# MSP-EXP430F5529LP.net
KiCad netlist of a schematic drawn in EAGLE
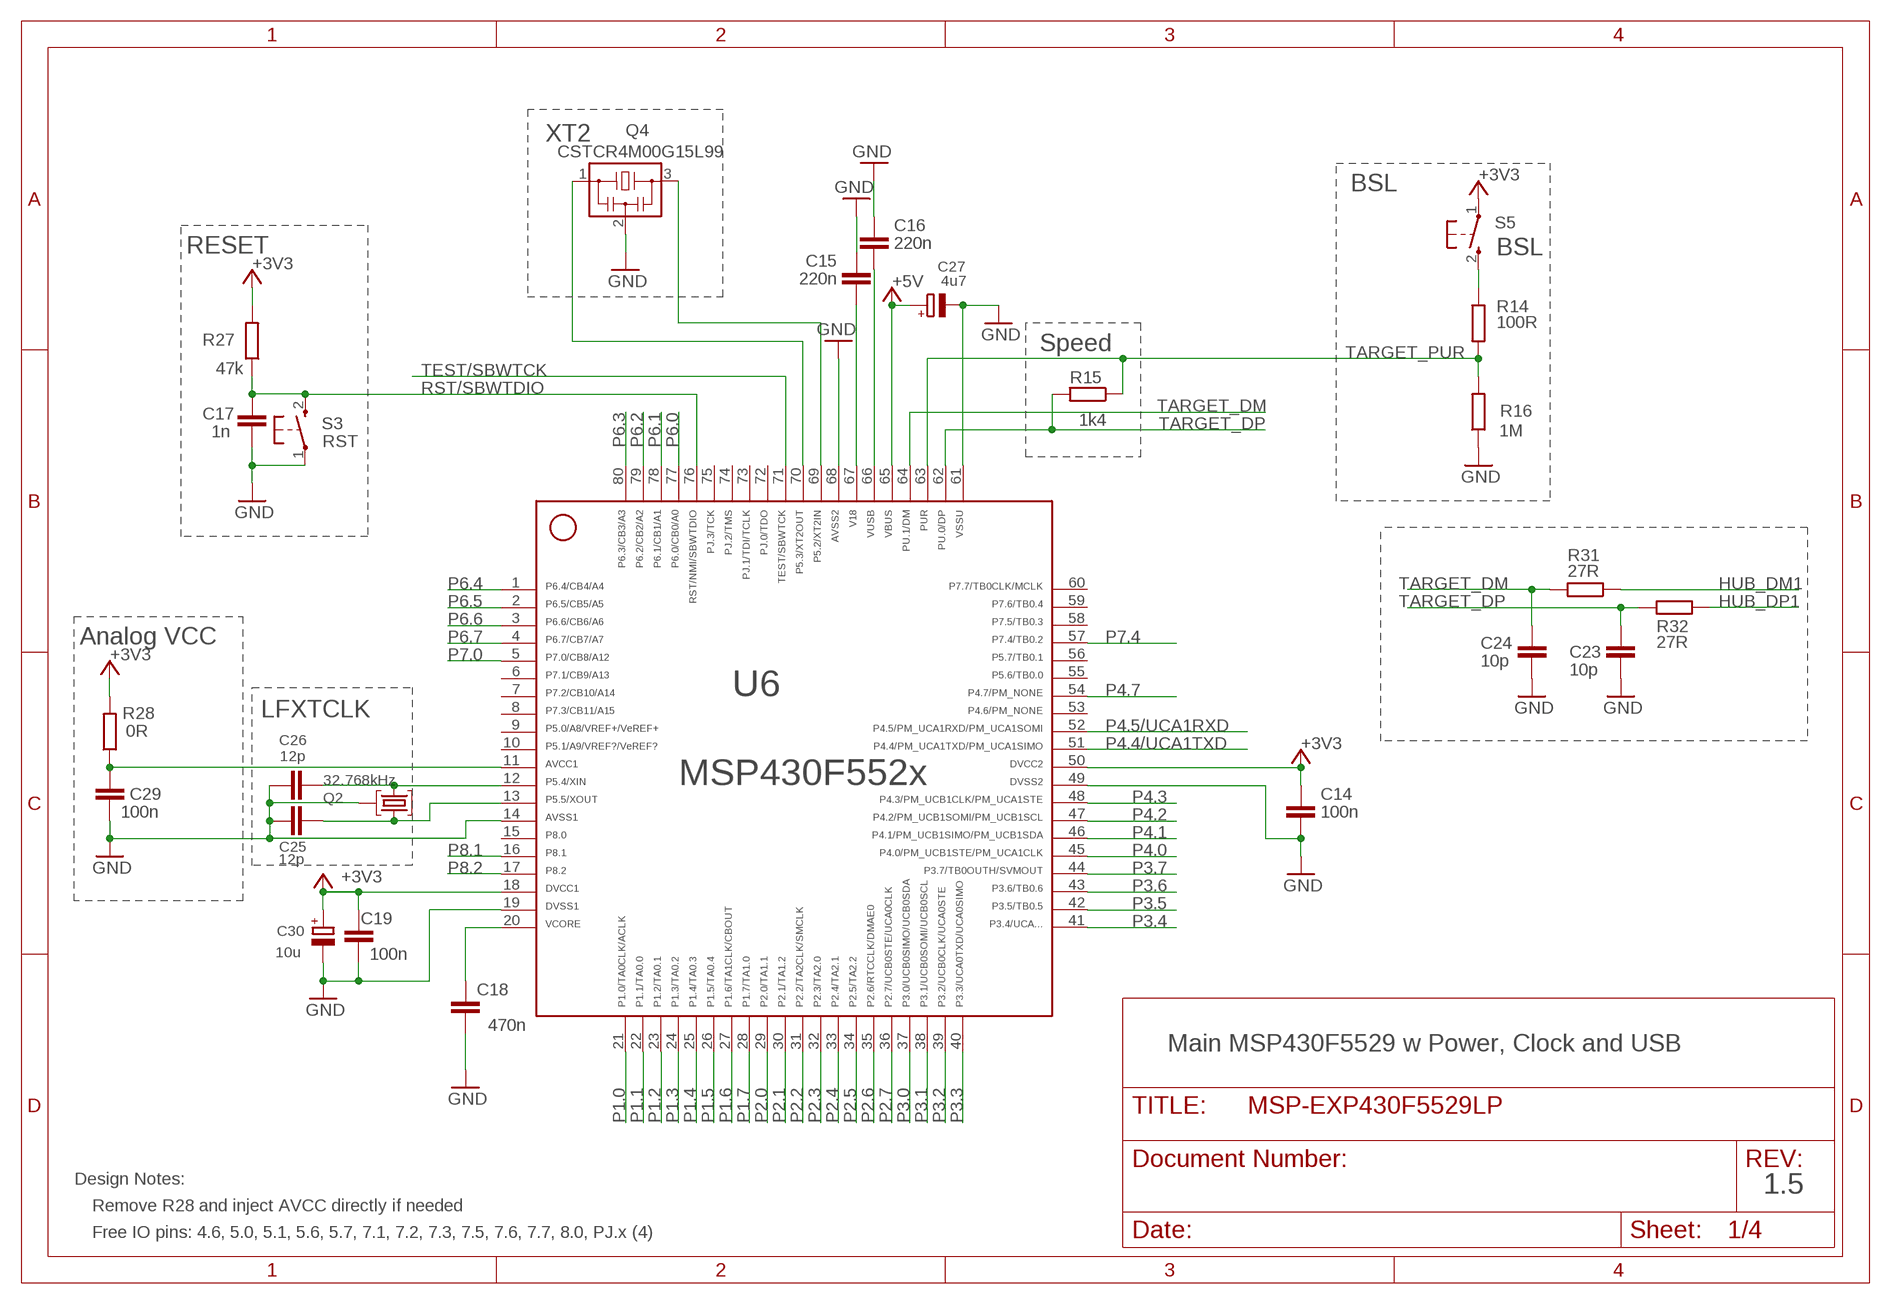
[diagram p0: schematic, sheet 1]
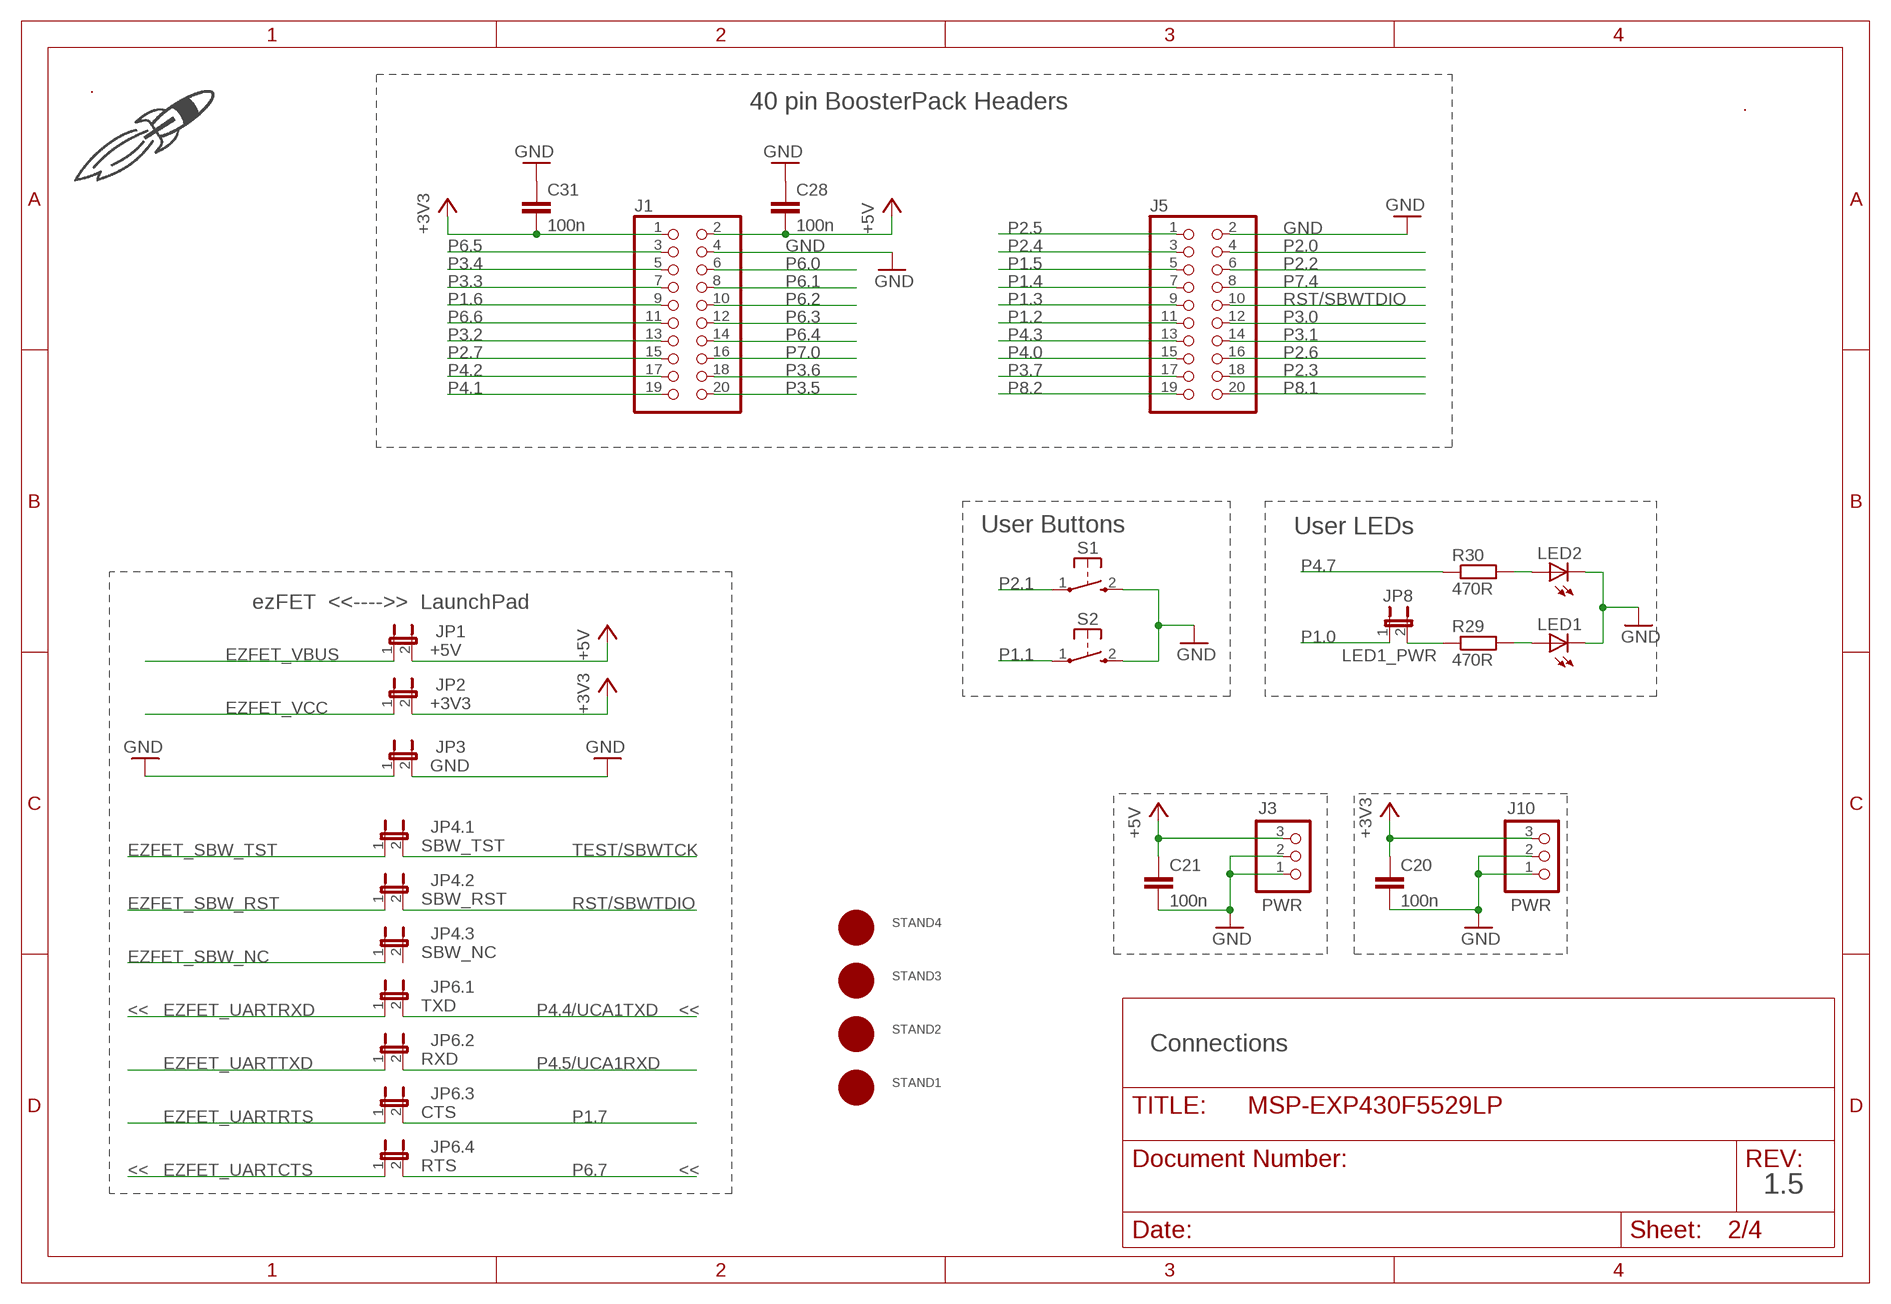
[diagram p1: schematic, sheet 2]
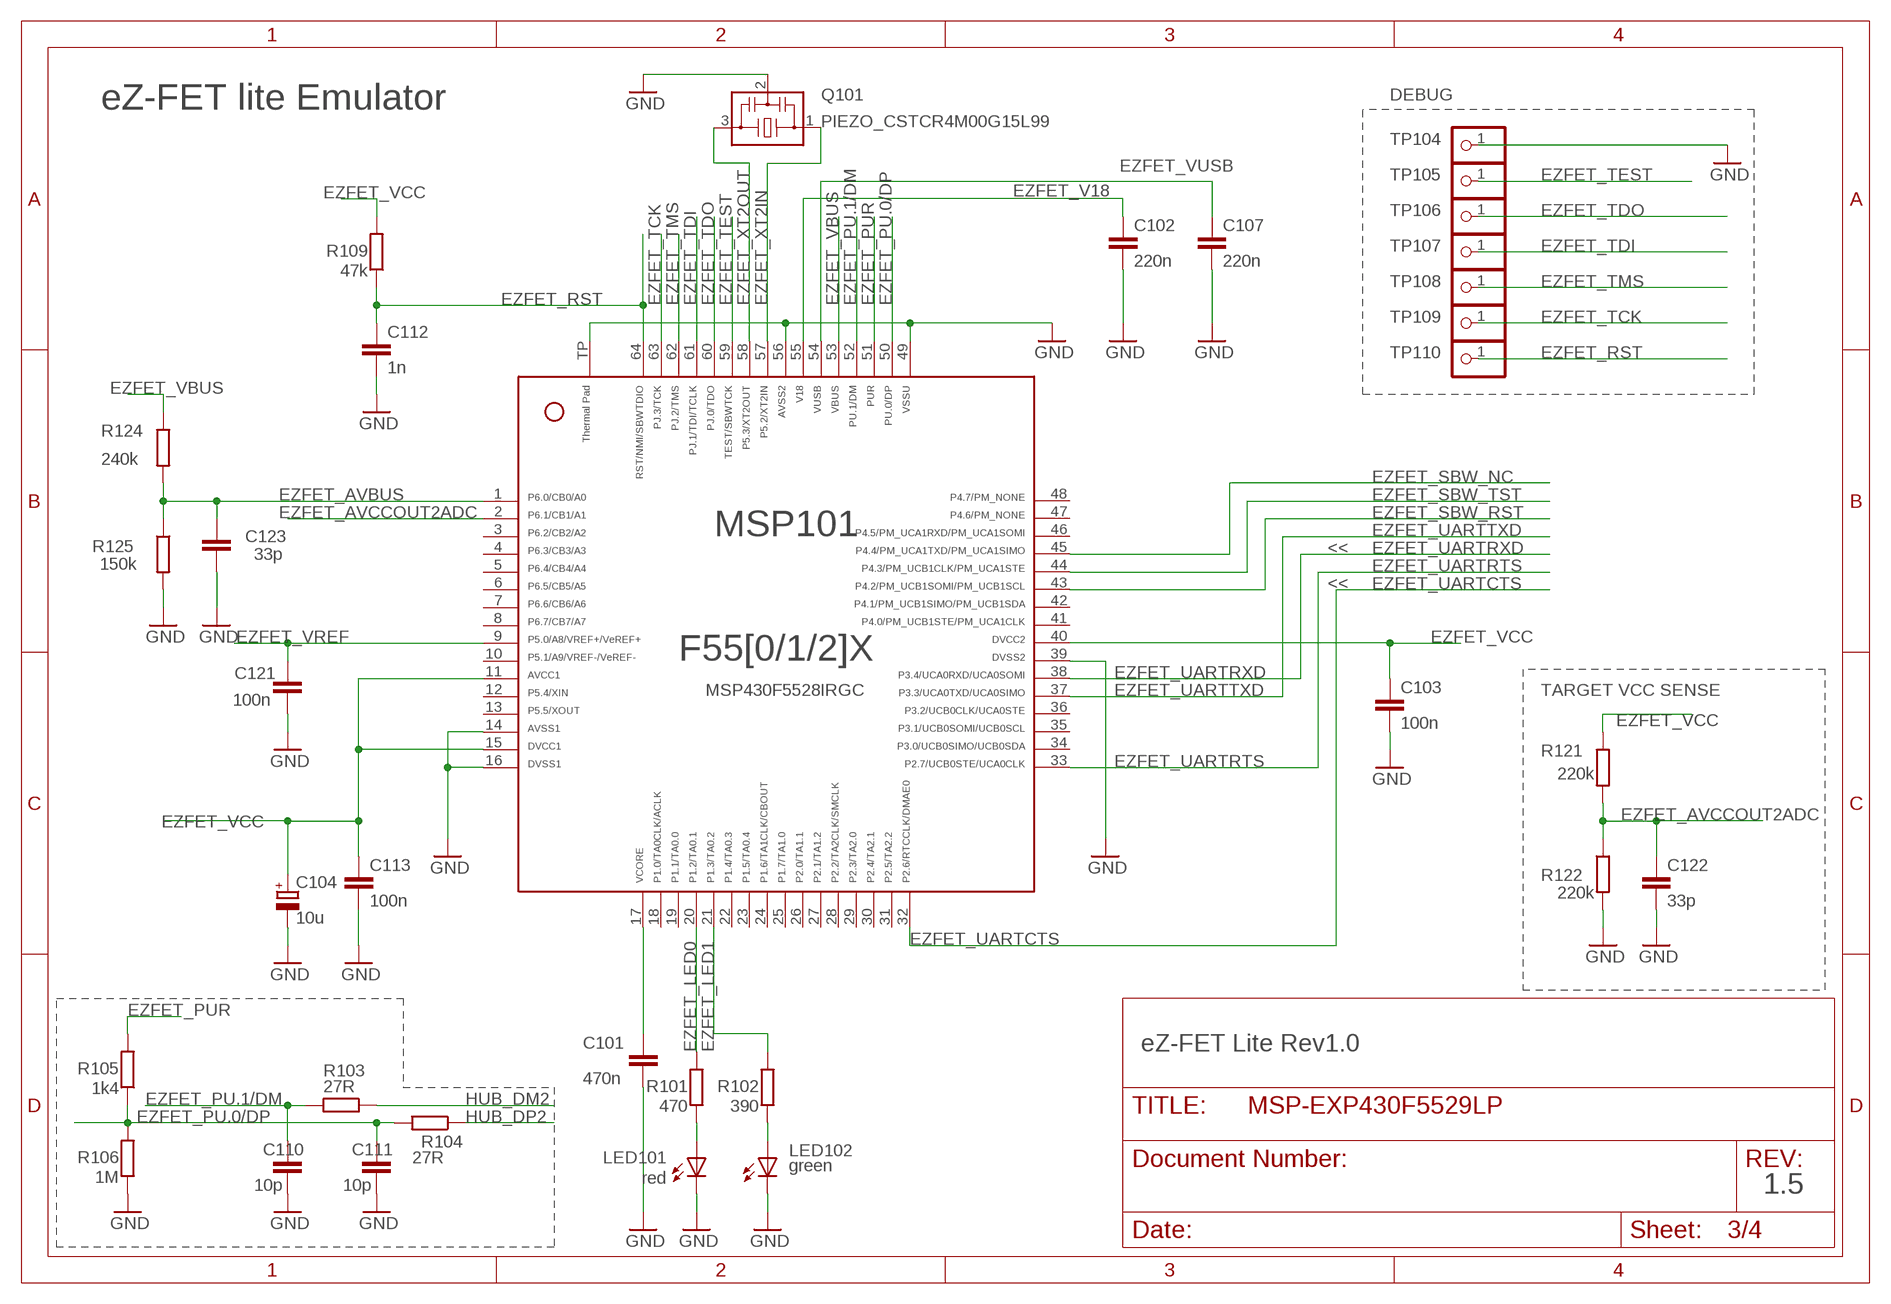
[diagram p2: schematic, sheet 3]
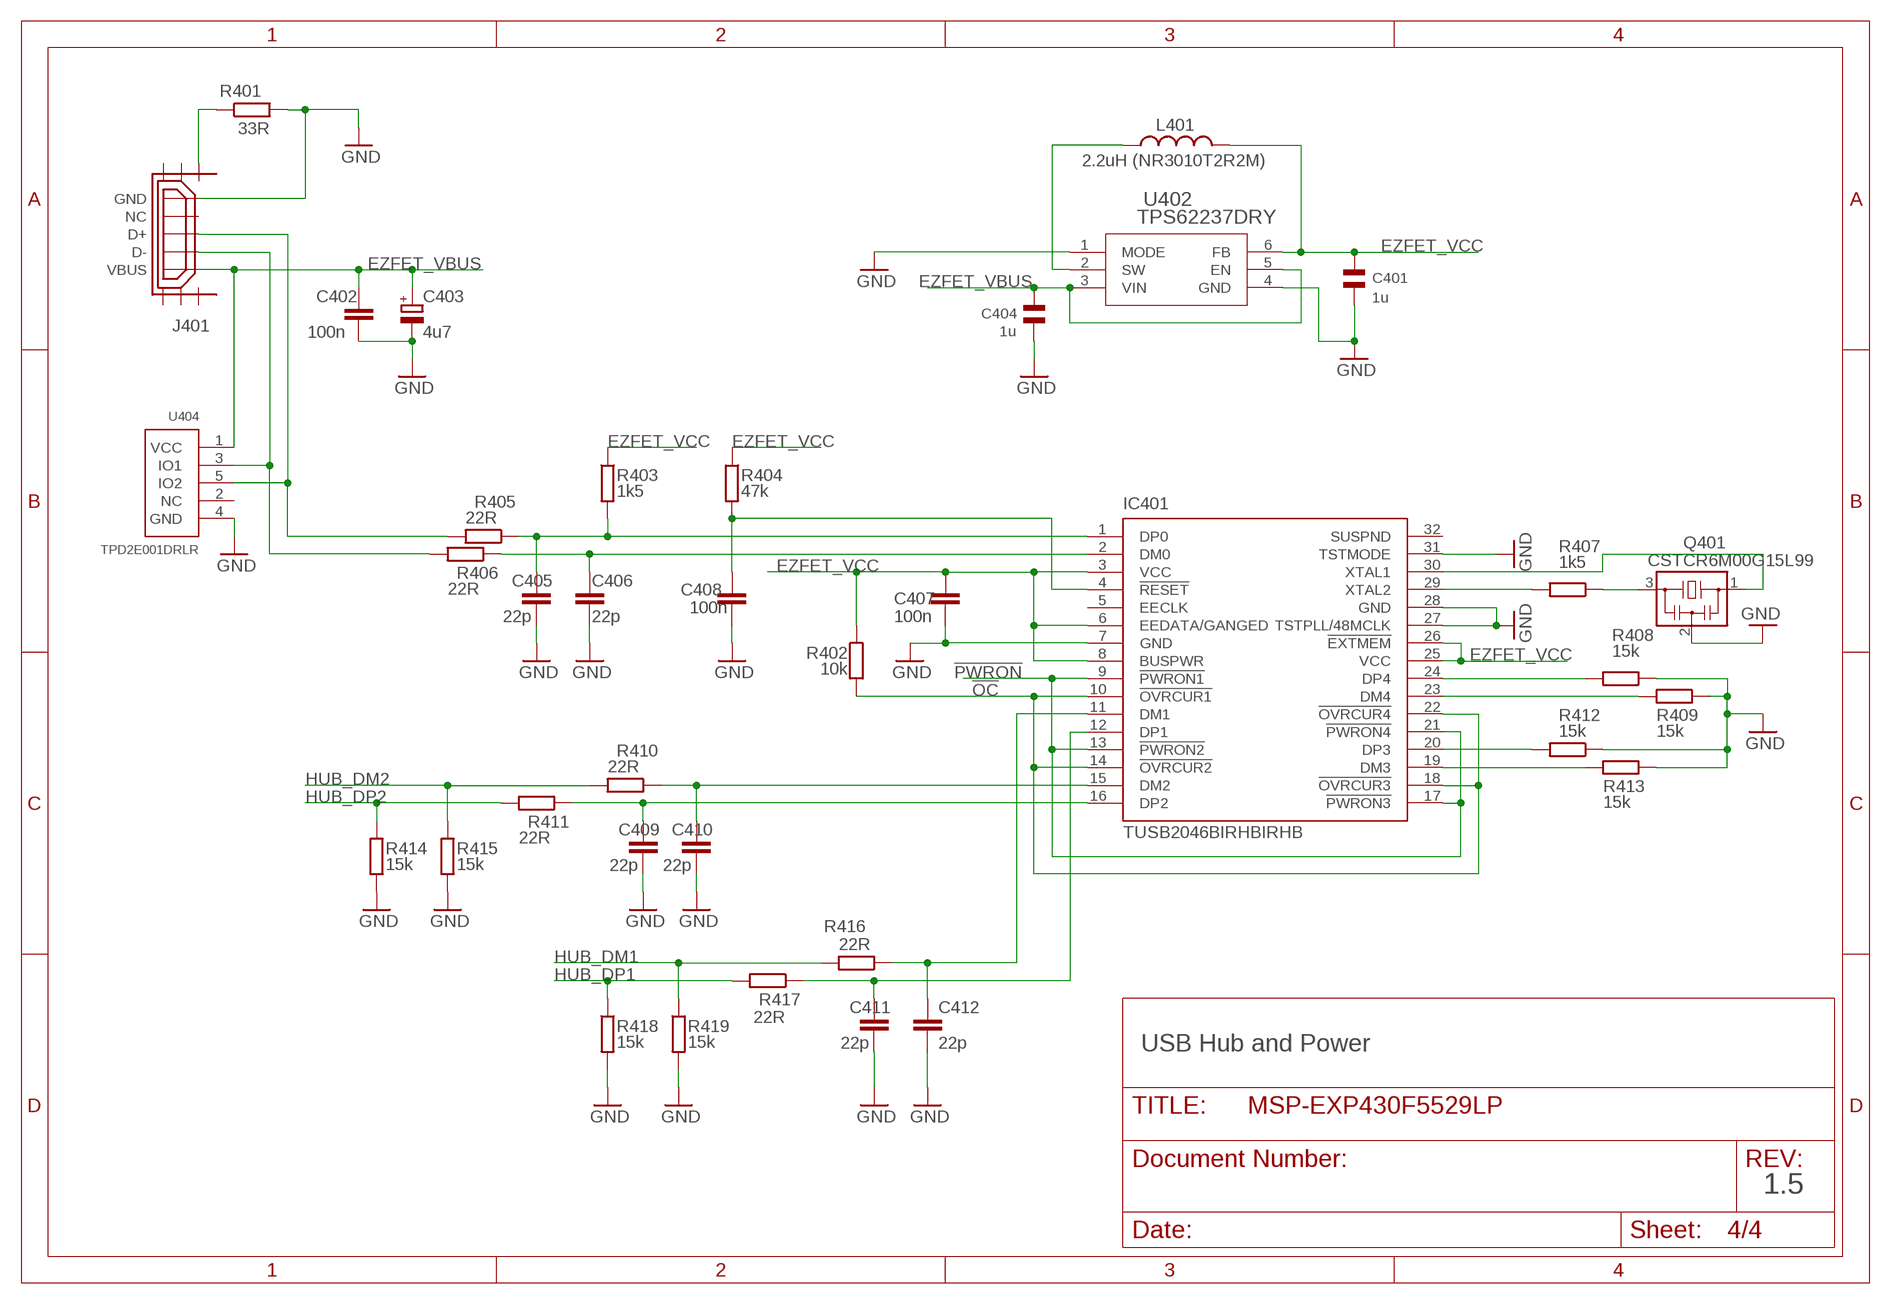
[diagram p3: schematic, sheet 4]

(export (version "E")
  (design (tool "Eeschema 10.0.6"))
  (components
    (comp (ref "C20")
      (value "100n")
      (footprint "eagle-import:C0402")
      (libsource (lib "eagle-import") (part "C-EUC0402"))
    )
    (comp (ref "C21")
      (value "100n")
      (footprint "eagle-import:C0402")
      (libsource (lib "eagle-import") (part "C-EUC0402"))
    )
    (comp (ref "C28")
      (value "100n")
      (footprint "eagle-import:C0402")
      (libsource (lib "eagle-import") (part "C-EUC0402"))
    )
    (comp (ref "C31")
      (value "100n")
      (footprint "eagle-import:C0402")
      (libsource (lib "eagle-import") (part "C-EUC0402"))
    )
    (comp (ref "DRAW1")
      (value "LOGO-ROCKET-20X13MM-SCH-S")
      (footprint "eagle-import:LOGO-ROCKET-10X7MM-BRD")
      (libsource (lib "eagle-import") (part "LOGO-ROCKET-20X13MM-SCH-S"))
    )
    (comp (ref "J1")
      (value "PINHD-2X10")
      (footprint "eagle-import:2X10")
      (libsource (lib "eagle-import") (part "PINHD-2X10"))
    )
    (comp (ref "J3")
      (value "PWR")
      (footprint "eagle-import:1X03")
      (libsource (lib "eagle-import") (part "PINHD-1X3"))
    )
    (comp (ref "J5")
      (value "PINHD-2X10")
      (footprint "eagle-import:2X10")
      (libsource (lib "eagle-import") (part "PINHD-2X10"))
    )
    (comp (ref "J10")
      (value "PWR")
      (footprint "eagle-import:1X03")
      (libsource (lib "eagle-import") (part "PINHD-1X3"))
    )
    (comp (ref "JP1")
      (value "+5V")
      (footprint "eagle-import:JP1M")
      (libsource (lib "eagle-import") (part "JP1M"))
    )
    (comp (ref "JP2")
      (value "+3V3")
      (footprint "eagle-import:JP1M")
      (libsource (lib "eagle-import") (part "JP1M"))
    )
    (comp (ref "JP3")
      (value "GND")
      (footprint "eagle-import:JP1M")
      (libsource (lib "eagle-import") (part "JP1M"))
    )
    (comp (ref "JP4.1")
      (value "SBW_TST")
      (footprint "eagle-import:JP1M")
      (libsource (lib "eagle-import") (part "JP1M"))
    )
    (comp (ref "JP4.2")
      (value "SBW_RST")
      (footprint "eagle-import:JP1M")
      (libsource (lib "eagle-import") (part "JP1M"))
    )
    (comp (ref "JP4.3")
      (value "SBW_NC")
      (footprint "eagle-import:JP1M")
      (libsource (lib "eagle-import") (part "JP1M"))
    )
    (comp (ref "JP6.1")
      (value "TXD")
      (footprint "eagle-import:JP1M")
      (libsource (lib "eagle-import") (part "JP1M"))
    )
    (comp (ref "JP6.2")
      (value "RXD")
      (footprint "eagle-import:JP1M")
      (libsource (lib "eagle-import") (part "JP1M"))
    )
    (comp (ref "JP6.3")
      (value "CTS")
      (footprint "eagle-import:JP1M")
      (libsource (lib "eagle-import") (part "JP1M"))
    )
    (comp (ref "JP6.4")
      (value "RTS")
      (footprint "eagle-import:JP1M")
      (libsource (lib "eagle-import") (part "JP1M"))
    )
    (comp (ref "JP8")
      (value "LED1_PWR")
      (footprint "eagle-import:JP1")
      (libsource (lib "eagle-import") (part "JP1E"))
    )
    (comp (ref "LED1")
      (value "LEDCHIP-LED0603")
      (footprint "eagle-import:CHIP-LED0603")
      (libsource (lib "eagle-import") (part "LEDCHIP-LED0603"))
    )
    (comp (ref "LED2")
      (value "LEDCHIP-LED0603")
      (footprint "eagle-import:CHIP-LED0603")
      (libsource (lib "eagle-import") (part "LEDCHIP-LED0603"))
    )
    (comp (ref "R29")
      (value "470R")
      (footprint "eagle-import:R0402")
      (libsource (lib "eagle-import") (part "R-EU_R0402"))
    )
    (comp (ref "R30")
      (value "470R")
      (footprint "eagle-import:R0402")
      (libsource (lib "eagle-import") (part "R-EU_R0402"))
    )
    (comp (ref "S1")
      (value "PB")
      (footprint "eagle-import:PBTH")
      (libsource (lib "eagle-import") (part "PB"))
    )
    (comp (ref "S2")
      (value "PB")
      (footprint "eagle-import:PBTH")
      (libsource (lib "eagle-import") (part "PB"))
    )
    (comp (ref "STAND1")
      (value "MOUNT")
      (footprint "eagle-import:MOUNTHOLE_110MIL")
      (libsource (lib "eagle-import") (part "MOUNT"))
    )
    (comp (ref "STAND2")
      (value "MOUNT")
      (footprint "eagle-import:MOUNTHOLE_110MIL")
      (libsource (lib "eagle-import") (part "MOUNT"))
    )
    (comp (ref "STAND3")
      (value "MOUNT")
      (footprint "eagle-import:MOUNTHOLE_110MIL")
      (libsource (lib "eagle-import") (part "MOUNT"))
    )
    (comp (ref "STAND4")
      (value "MOUNT")
      (footprint "eagle-import:MOUNTHOLE_110MIL")
      (libsource (lib "eagle-import") (part "MOUNT"))
    )
    (comp (ref "U$3")
      (value "5529_REAR_SILK_REV1_5_FINAL")
      (footprint "eagle-import:5529_REAR_SILK_REV1_5_FINAL")
      (libsource (lib "eagle-import") (part "5529_REAR_SILK_REV1_5_FINAL"))
    )
    (comp (ref "U$4")
      (value "MS_TM")
      (footprint "eagle-import:MS_TM")
      (libsource (lib "eagle-import") (part "MS_TM"))
    )
    (comp (ref "C14")
      (value "100n")
      (footprint "eagle-import:C0402")
      (libsource (lib "eagle-import") (part "C-EUC0402"))
    )
    (comp (ref "C15")
      (value "220n")
      (footprint "eagle-import:C0402")
      (libsource (lib "eagle-import") (part "C-EUC0402"))
    )
    (comp (ref "C16")
      (value "220n")
      (footprint "eagle-import:C0402")
      (libsource (lib "eagle-import") (part "C-EUC0402"))
    )
    (comp (ref "C17")
      (value "1n")
      (footprint "eagle-import:C0402")
      (libsource (lib "eagle-import") (part "C-EUC0402"))
    )
    (comp (ref "C18")
      (value "470n")
      (footprint "eagle-import:C0402")
      (libsource (lib "eagle-import") (part "C-EUC0402"))
    )
    (comp (ref "C19")
      (value "100n")
      (footprint "eagle-import:C0402")
      (libsource (lib "eagle-import") (part "C-EUC0402"))
    )
    (comp (ref "C23")
      (value "10p")
      (footprint "eagle-import:C0402")
      (libsource (lib "eagle-import") (part "C-EUC0402"))
    )
    (comp (ref "C24")
      (value "10p")
      (footprint "eagle-import:C0402")
      (libsource (lib "eagle-import") (part "C-EUC0402"))
    )
    (comp (ref "C25")
      (value "12p")
      (footprint "eagle-import:C0402")
      (libsource (lib "eagle-import") (part "C-EUC0402"))
    )
    (comp (ref "C26")
      (value "12p")
      (footprint "eagle-import:C0402")
      (libsource (lib "eagle-import") (part "C-EUC0402"))
    )
    (comp (ref "C27")
      (value "4u7")
      (footprint "eagle-import:A_3216-18R")
      (libsource (lib "eagle-import") (part "CPOL-EUA/3216-18R"))
    )
    (comp (ref "C29")
      (value "100n")
      (footprint "eagle-import:C0402")
      (libsource (lib "eagle-import") (part "C-EUC0402"))
    )
    (comp (ref "C30")
      (value "10u")
      (footprint "eagle-import:A_3216-18R")
      (libsource (lib "eagle-import") (part "CPOL-EUA/3216-18R"))
    )
    (comp (ref "Q2")
      (value "32.768kHz")
      (footprint "eagle-import:MS3V-T1R")
      (libsource (lib "eagle-import") (part "MS3V-T1R"))
    )
    (comp (ref "Q4")
      (value "CSTCR4M00G15L99")
      (footprint "eagle-import:MURATA-FILTER_CSTCR")
      (fields (field (name "MPN") "CSTCR6M00G53-R0"))
      (libsource (lib "eagle-import") (part "MURATA-FILTER_CSTCR6M00G53Z"))
    )
    (comp (ref "R14")
      (value "100R")
      (footprint "eagle-import:R0402")
      (libsource (lib "eagle-import") (part "R-EU_R0402"))
    )
    (comp (ref "R15")
      (value "1k4")
      (footprint "eagle-import:R0402")
      (libsource (lib "eagle-import") (part "R-EU_R0402"))
    )
    (comp (ref "R16")
      (value "1M")
      (footprint "eagle-import:R0402")
      (libsource (lib "eagle-import") (part "R-EU_R0402"))
    )
    (comp (ref "R27")
      (value "47k")
      (footprint "eagle-import:R0402")
      (libsource (lib "eagle-import") (part "R-EU_R0402"))
    )
    (comp (ref "R28")
      (value "0R")
      (footprint "eagle-import:R0402")
      (libsource (lib "eagle-import") (part "R-EU_R0402"))
    )
    (comp (ref "R31")
      (value "27R")
      (footprint "eagle-import:R0402")
      (libsource (lib "eagle-import") (part "R-EU_R0402"))
    )
    (comp (ref "R32")
      (value "27R")
      (footprint "eagle-import:R0402")
      (libsource (lib "eagle-import") (part "R-EU_R0402"))
    )
    (comp (ref "S3")
      (value "RST")
      (footprint "eagle-import:PBTH")
      (libsource (lib "eagle-import") (part "PB"))
    )
    (comp (ref "S5")
      (value "BSL")
      (footprint "eagle-import:PBTH")
      (libsource (lib "eagle-import") (part "PB"))
    )
    (comp (ref "U6")
      (value "MSP430F5529IPNR")
      (footprint "eagle-import:PN80")
      (libsource (lib "eagle-import") (part "F552X---PN80"))
    )
    (comp (ref "C101")
      (value "470n")
      (footprint "eagle-import:C0402")
      (libsource (lib "eagle-import") (part "C-EUC0402"))
    )
    (comp (ref "C102")
      (value "220n")
      (footprint "eagle-import:C0402")
      (libsource (lib "eagle-import") (part "C-EUC0402"))
    )
    (comp (ref "C103")
      (value "100n")
      (footprint "eagle-import:C0402")
      (libsource (lib "eagle-import") (part "C-EUC0402"))
    )
    (comp (ref "C104")
      (value "10u")
      (footprint "eagle-import:A_3216-18R")
      (libsource (lib "eagle-import") (part "CPOL-EUA/3216-18R"))
    )
    (comp (ref "C107")
      (value "220n")
      (footprint "eagle-import:C0402")
      (libsource (lib "eagle-import") (part "C-EUC0402"))
    )
    (comp (ref "C110")
      (value "10p")
      (footprint "eagle-import:C0402")
      (libsource (lib "eagle-import") (part "C-EUC0402"))
    )
    (comp (ref "C111")
      (value "10p")
      (footprint "eagle-import:C0402")
      (libsource (lib "eagle-import") (part "C-EUC0402"))
    )
    (comp (ref "C112")
      (value "1n")
      (footprint "eagle-import:C0402")
      (libsource (lib "eagle-import") (part "C-EUC0402"))
    )
    (comp (ref "C113")
      (value "100n")
      (footprint "eagle-import:C0402")
      (libsource (lib "eagle-import") (part "C-EUC0402"))
    )
    (comp (ref "C121")
      (value "100n")
      (footprint "eagle-import:C0402")
      (libsource (lib "eagle-import") (part "C-EUC0402"))
    )
    (comp (ref "C122")
      (value "33p")
      (footprint "eagle-import:C0402")
      (libsource (lib "eagle-import") (part "C-EUC0402"))
    )
    (comp (ref "C123")
      (value "33p")
      (footprint "eagle-import:C0402")
      (libsource (lib "eagle-import") (part "C-EUC0402"))
    )
    (comp (ref "LED101")
      (value "red")
      (footprint "eagle-import:CHIP-LED0603")
      (libsource (lib "eagle-import") (part "LEDCHIP-LED0603"))
    )
    (comp (ref "LED102")
      (value "green")
      (footprint "eagle-import:CHIP-LED0603")
      (libsource (lib "eagle-import") (part "LEDCHIP-LED0603"))
    )
    (comp (ref "MSP101")
      (value "MSP430F5528IRGC")
      (footprint "eagle-import:RGC64")
      (libsource (lib "eagle-import") (part "F55[0/1/2]X---RGC64"))
    )
    (comp (ref "Q101")
      (value "PIEZO_CSTCR4M00G15L99")
      (footprint "eagle-import:MURATA-FILTER_CSTCR")
      (fields (field (name "MPN") "CSTCR6M00G53-R0"))
      (libsource (lib "eagle-import") (part "MURATA-FILTER_CSTCR6M00G53Z"))
    )
    (comp (ref "R101")
      (value "470")
      (footprint "eagle-import:R0402")
      (libsource (lib "eagle-import") (part "R-EU_R0402"))
    )
    (comp (ref "R102")
      (value "390")
      (footprint "eagle-import:R0402")
      (libsource (lib "eagle-import") (part "R-EU_R0402"))
    )
    (comp (ref "R103")
      (value "27R")
      (footprint "eagle-import:R0402")
      (libsource (lib "eagle-import") (part "R-EU_R0402"))
    )
    (comp (ref "R104")
      (value "27R")
      (footprint "eagle-import:R0402")
      (libsource (lib "eagle-import") (part "R-EU_R0402"))
    )
    (comp (ref "R105")
      (value "1k4")
      (footprint "eagle-import:R0402")
      (libsource (lib "eagle-import") (part "R-EU_R0402"))
    )
    (comp (ref "R106")
      (value "1M")
      (footprint "eagle-import:R0402")
      (libsource (lib "eagle-import") (part "R-EU_R0402"))
    )
    (comp (ref "R109")
      (value "47k")
      (footprint "eagle-import:R0402")
      (libsource (lib "eagle-import") (part "R-EU_R0402"))
    )
    (comp (ref "R121")
      (value "220k")
      (footprint "eagle-import:R0402")
      (libsource (lib "eagle-import") (part "R-EU_R0402"))
    )
    (comp (ref "R122")
      (value "220k")
      (footprint "eagle-import:R0402")
      (libsource (lib "eagle-import") (part "R-EU_R0402"))
    )
    (comp (ref "R124")
      (value "240k")
      (footprint "eagle-import:R0402")
      (libsource (lib "eagle-import") (part "R-EU_R0402"))
    )
    (comp (ref "R125")
      (value "150k")
      (footprint "eagle-import:R0402")
      (libsource (lib "eagle-import") (part "R-EU_R0402"))
    )
    (comp (ref "TP104")
      (value "TEST_PIN2")
      (footprint "eagle-import:1X01")
      (libsource (lib "eagle-import") (part "PINHD-1X1"))
    )
    (comp (ref "TP105")
      (value "TEST_PIN2")
      (footprint "eagle-import:1X01")
      (libsource (lib "eagle-import") (part "PINHD-1X1"))
    )
    (comp (ref "TP106")
      (value "TEST_PIN2")
      (footprint "eagle-import:1X01")
      (libsource (lib "eagle-import") (part "PINHD-1X1"))
    )
    (comp (ref "TP107")
      (value "TEST_PIN2")
      (footprint "eagle-import:1X01")
      (libsource (lib "eagle-import") (part "PINHD-1X1"))
    )
    (comp (ref "TP108")
      (value "TEST_PIN2")
      (footprint "eagle-import:1X01")
      (libsource (lib "eagle-import") (part "PINHD-1X1"))
    )
    (comp (ref "TP109")
      (value "TEST_PIN2")
      (footprint "eagle-import:1X01")
      (libsource (lib "eagle-import") (part "PINHD-1X1"))
    )
    (comp (ref "TP110")
      (value "TEST_PIN2")
      (footprint "eagle-import:1X01")
      (libsource (lib "eagle-import") (part "PINHD-1X1"))
    )
    (comp (ref "C401")
      (value "1u")
      (footprint "eagle-import:CSMD0805")
      (libsource (lib "eagle-import") (part "CSMD0805"))
    )
    (comp (ref "C402")
      (value "100n")
      (footprint "eagle-import:C0402")
      (libsource (lib "eagle-import") (part "C-EUC0402"))
    )
    (comp (ref "C403")
      (value "4u7")
      (footprint "eagle-import:A_3216-18R")
      (libsource (lib "eagle-import") (part "CPOL-EUA/3216-18R"))
    )
    (comp (ref "C404")
      (value "1u")
      (footprint "eagle-import:CSMD0805")
      (libsource (lib "eagle-import") (part "CSMD0805"))
    )
    (comp (ref "C405")
      (value "22p")
      (footprint "eagle-import:C0402")
      (libsource (lib "eagle-import") (part "C-EUC0402"))
    )
    (comp (ref "C406")
      (value "22p")
      (footprint "eagle-import:C0402")
      (libsource (lib "eagle-import") (part "C-EUC0402"))
    )
    (comp (ref "C407")
      (value "100n")
      (footprint "eagle-import:C0402")
      (libsource (lib "eagle-import") (part "C-EUC0402"))
    )
    (comp (ref "C408")
      (value "100n")
      (footprint "eagle-import:C0402")
      (libsource (lib "eagle-import") (part "C-EUC0402"))
    )
    (comp (ref "C409")
      (value "22p")
      (footprint "eagle-import:C0402")
      (libsource (lib "eagle-import") (part "C-EUC0402"))
    )
    (comp (ref "C410")
      (value "22p")
      (footprint "eagle-import:C0402")
      (libsource (lib "eagle-import") (part "C-EUC0402"))
    )
    (comp (ref "C411")
      (value "22p")
      (footprint "eagle-import:C0402")
      (libsource (lib "eagle-import") (part "C-EUC0402"))
    )
    (comp (ref "C412")
      (value "22p")
      (footprint "eagle-import:C0402")
      (libsource (lib "eagle-import") (part "C-EUC0402"))
    )
    (comp (ref "IC401")
      (value "TUSB2046BIRHBIRHB")
      (footprint "eagle-import:RHB_S-PQFP-N32")
      (fields (field (name "MPN") "TUSB2046BIRHBT"))
      (libsource (lib "eagle-import") (part "TUSB2046BIRHBIRHB"))
    )
    (comp (ref "J401")
      (value "USB_MICRO_FLIPPED")
      (footprint "eagle-import:HIROSE-ZX62R-B-5P")
      (libsource (lib "eagle-import") (part "USB_MICRO_FLIPPED"))
    )
    (comp (ref "L401")
      (value "2.2uH (NR3010T2R2M)")
      (footprint "eagle-import:L-NR3010")
      (libsource (lib "eagle-import") (part "L-NR3010"))
    )
    (comp (ref "Q401")
      (value "CSTCR6M00G15L99")
      (footprint "eagle-import:MURATA-FILTER_CSTCR")
      (fields (field (name "MPN") "CSTCR6M00G53-R0"))
      (libsource (lib "eagle-import") (part "MURATA-FILTER_CSTCR6M00G53Z"))
    )
    (comp (ref "R401")
      (value "33R")
      (footprint "eagle-import:R0402")
      (libsource (lib "eagle-import") (part "R-EU_R0402"))
    )
    (comp (ref "R402")
      (value "10k")
      (footprint "eagle-import:R0402")
      (libsource (lib "eagle-import") (part "R-EU_R0402"))
    )
    (comp (ref "R403")
      (value "1k5")
      (footprint "eagle-import:R0402")
      (libsource (lib "eagle-import") (part "R-EU_R0402"))
    )
    (comp (ref "R404")
      (value "47k")
      (footprint "eagle-import:R0402")
      (libsource (lib "eagle-import") (part "R-EU_R0402"))
    )
    (comp (ref "R405")
      (value "22R")
      (footprint "eagle-import:R0402")
      (libsource (lib "eagle-import") (part "R-EU_R0402"))
    )
    (comp (ref "R406")
      (value "22R")
      (footprint "eagle-import:R0402")
      (libsource (lib "eagle-import") (part "R-EU_R0402"))
    )
    (comp (ref "R407")
      (value "1k5")
      (footprint "eagle-import:R0402")
      (libsource (lib "eagle-import") (part "R-EU_R0402"))
    )
    (comp (ref "R408")
      (value "15k")
      (footprint "eagle-import:R0402")
      (libsource (lib "eagle-import") (part "R-EU_R0402"))
    )
    (comp (ref "R409")
      (value "15k")
      (footprint "eagle-import:R0402")
      (libsource (lib "eagle-import") (part "R-EU_R0402"))
    )
    (comp (ref "R410")
      (value "22R")
      (footprint "eagle-import:R0402")
      (libsource (lib "eagle-import") (part "R-EU_R0402"))
    )
    (comp (ref "R411")
      (value "22R")
      (footprint "eagle-import:R0402")
      (libsource (lib "eagle-import") (part "R-EU_R0402"))
    )
    (comp (ref "R412")
      (value "15k")
      (footprint "eagle-import:R0402")
      (libsource (lib "eagle-import") (part "R-EU_R0402"))
    )
    (comp (ref "R413")
      (value "15k")
      (footprint "eagle-import:R0402")
      (libsource (lib "eagle-import") (part "R-EU_R0402"))
    )
    (comp (ref "R414")
      (value "15k")
      (footprint "eagle-import:R0402")
      (libsource (lib "eagle-import") (part "R-EU_R0402"))
    )
    (comp (ref "R415")
      (value "15k")
      (footprint "eagle-import:R0402")
      (libsource (lib "eagle-import") (part "R-EU_R0402"))
    )
    (comp (ref "R416")
      (value "22R")
      (footprint "eagle-import:R0402")
      (libsource (lib "eagle-import") (part "R-EU_R0402"))
    )
    (comp (ref "R417")
      (value "22R")
      (footprint "eagle-import:R0402")
      (libsource (lib "eagle-import") (part "R-EU_R0402"))
    )
    (comp (ref "R418")
      (value "15k")
      (footprint "eagle-import:R0402")
      (libsource (lib "eagle-import") (part "R-EU_R0402"))
    )
    (comp (ref "R419")
      (value "15k")
      (footprint "eagle-import:R0402")
      (libsource (lib "eagle-import") (part "R-EU_R0402"))
    )
    (comp (ref "U402")
      (value "TPS62237DRY")
      (footprint "eagle-import:DRY6")
      (fields
        (field (name "GENERIC_PART_NUMBER") "TPS62231")
        (field (name "MANUFACTURER") "Texas Instruments")
        (field (name "MANUFACTURER_PART_NUMBER") "tps62231_dry_6")
      )
      (libsource (lib "eagle-import") (part "TPS6223X_DRY_6"))
    )
    (comp (ref "U404")
      (value "TPD2E001DRLR")
      (footprint "eagle-import:TPD2E001-DRL")
      (libsource (lib "eagle-import") (part "TPD2E001"))
    )
  )
  (nets
    (net (code "1") (name "+3V3") (class "Default")
      (node (ref "C14") (pin "1") (pinfunction "1_1") (pintype "passive"))
      (node (ref "C19") (pin "2") (pinfunction "2_2") (pintype "passive"))
      (node (ref "C20") (pin "1") (pinfunction "1_1") (pintype "passive"))
      (node (ref "C30") (pin "+") (pinfunction "+_+") (pintype "passive"))
      (node (ref "C31") (pin "2") (pinfunction "2_2") (pintype "passive"))
      (node (ref "J1") (pin "1") (pinfunction "1_1") (pintype "passive"))
      (node (ref "J10") (pin "3") (pinfunction "3_3") (pintype "passive"))
      (node (ref "JP2") (pin "2") (pinfunction "2_2") (pintype "passive"))
      (node (ref "R27") (pin "2") (pinfunction "2_2") (pintype "passive"))
      (node (ref "R28") (pin "2") (pinfunction "2_2") (pintype "passive"))
      (node (ref "S5") (pin "1") (pinfunction "P_1") (pintype "passive"))
      (node (ref "U6") (pin "18") (pinfunction "18_18") (pintype "power_in"))
      (node (ref "U6") (pin "50") (pinfunction "50_50") (pintype "power_in"))
    )
    (net (code "2") (name "+5V") (class "Default")
      (node (ref "C21") (pin "1") (pinfunction "1_1") (pintype "passive"))
      (node (ref "C27") (pin "+") (pinfunction "+_+") (pintype "passive"))
      (node (ref "C28") (pin "2") (pinfunction "2_2") (pintype "passive"))
      (node (ref "J1") (pin "2") (pinfunction "2_2") (pintype "passive"))
      (node (ref "J3") (pin "3") (pinfunction "3_3") (pintype "passive"))
      (node (ref "JP1") (pin "2") (pinfunction "2_2") (pintype "passive"))
      (node (ref "U6") (pin "65") (pinfunction "65_65") (pintype "power_in"))
    )
    (net (code "3") (name "EZFET_AVBUS") (class "Default")
      (node (ref "C123") (pin "2") (pinfunction "2_2") (pintype "passive"))
      (node (ref "MSP101") (pin "1") (pinfunction "1_1") (pintype "bidirectional"))
      (node (ref "R124") (pin "2") (pinfunction "2_2") (pintype "passive"))
      (node (ref "R125") (pin "1") (pinfunction "1_1") (pintype "passive"))
    )
    (net (code "4") (name "EZFET_AVCCOUT2ADC") (class "Default")
      (node (ref "C122") (pin "2") (pinfunction "2_2") (pintype "passive"))
      (node (ref "MSP101") (pin "2") (pinfunction "2_2") (pintype "bidirectional"))
      (node (ref "R121") (pin "2") (pinfunction "2_2") (pintype "passive"))
      (node (ref "R122") (pin "1") (pinfunction "1_1") (pintype "passive"))
    )
    (net (code "5") (name "EZFET_LED0") (class "Default")
      (node (ref "MSP101") (pin "20") (pinfunction "20_20") (pintype "bidirectional"))
      (node (ref "R101") (pin "2") (pinfunction "2_2") (pintype "passive"))
    )
    (net (code "6") (name "EZFET_LED1") (class "Default")
      (node (ref "MSP101") (pin "21") (pinfunction "21_21") (pintype "bidirectional"))
      (node (ref "R102") (pin "2") (pinfunction "2_2") (pintype "passive"))
    )
    (net (code "7") (name "EZFET_PU.0{slash}DP") (class "Default")
      (node (ref "C111") (pin "1") (pinfunction "1_1") (pintype "passive"))
      (node (ref "MSP101") (pin "50") (pinfunction "50_50") (pintype "bidirectional"))
      (node (ref "R104") (pin "2") (pinfunction "2_2") (pintype "passive"))
      (node (ref "R105") (pin "1") (pinfunction "1_1") (pintype "passive"))
      (node (ref "R106") (pin "2") (pinfunction "2_2") (pintype "passive"))
    )
    (net (code "8") (name "EZFET_PU.1{slash}DM") (class "Default")
      (node (ref "C110") (pin "1") (pinfunction "1_1") (pintype "passive"))
      (node (ref "MSP101") (pin "52") (pinfunction "52_52") (pintype "bidirectional"))
      (node (ref "R103") (pin "2") (pinfunction "2_2") (pintype "passive"))
    )
    (net (code "9") (name "EZFET_PUR") (class "Default")
      (node (ref "MSP101") (pin "51") (pinfunction "51_51") (pintype "bidirectional"))
      (node (ref "R105") (pin "2") (pinfunction "2_2") (pintype "passive"))
    )
    (net (code "10") (name "EZFET_RST") (class "Default")
      (node (ref "C112") (pin "1") (pinfunction "1_1") (pintype "passive"))
      (node (ref "MSP101") (pin "64") (pinfunction "64_64") (pintype "bidirectional"))
      (node (ref "R109") (pin "1") (pinfunction "1_1") (pintype "passive"))
      (node (ref "TP110") (pin "1") (pinfunction "1_1") (pintype "passive"))
    )
    (net (code "11") (name "EZFET_SBW_NC") (class "Default")
      (node (ref "JP4.3") (pin "1") (pinfunction "1_1") (pintype "passive"))
      (node (ref "MSP101") (pin "45") (pinfunction "45_45") (pintype "bidirectional"))
    )
    (net (code "12") (name "EZFET_SBW_RST") (class "Default")
      (node (ref "JP4.2") (pin "1") (pinfunction "1_1") (pintype "passive"))
      (node (ref "MSP101") (pin "43") (pinfunction "43_43") (pintype "bidirectional"))
    )
    (net (code "13") (name "EZFET_SBW_TST") (class "Default")
      (node (ref "JP4.1") (pin "1") (pinfunction "1_1") (pintype "passive"))
      (node (ref "MSP101") (pin "44") (pinfunction "44_44") (pintype "bidirectional"))
    )
    (net (code "14") (name "EZFET_TCK") (class "Default")
      (node (ref "MSP101") (pin "63") (pinfunction "63_63") (pintype "bidirectional"))
      (node (ref "TP109") (pin "1") (pinfunction "1_1") (pintype "passive"))
    )
    (net (code "15") (name "EZFET_TDI") (class "Default")
      (node (ref "MSP101") (pin "61") (pinfunction "61_61") (pintype "bidirectional"))
      (node (ref "TP107") (pin "1") (pinfunction "1_1") (pintype "passive"))
    )
    (net (code "16") (name "EZFET_TDO") (class "Default")
      (node (ref "MSP101") (pin "60") (pinfunction "60_60") (pintype "bidirectional"))
      (node (ref "TP106") (pin "1") (pinfunction "1_1") (pintype "passive"))
    )
    (net (code "17") (name "EZFET_TEST") (class "Default")
      (node (ref "MSP101") (pin "59") (pinfunction "59_59") (pintype "input"))
      (node (ref "TP105") (pin "1") (pinfunction "1_1") (pintype "passive"))
    )
    (net (code "18") (name "EZFET_TMS") (class "Default")
      (node (ref "MSP101") (pin "62") (pinfunction "62_62") (pintype "bidirectional"))
      (node (ref "TP108") (pin "1") (pinfunction "1_1") (pintype "passive"))
    )
    (net (code "19") (name "EZFET_UARTCTS") (class "Default")
      (node (ref "JP6.4") (pin "1") (pinfunction "1_1") (pintype "passive"))
      (node (ref "MSP101") (pin "32") (pinfunction "32_32") (pintype "bidirectional"))
    )
    (net (code "20") (name "EZFET_UARTRTS") (class "Default")
      (node (ref "JP6.3") (pin "1") (pinfunction "1_1") (pintype "passive"))
      (node (ref "MSP101") (pin "33") (pinfunction "33_33") (pintype "bidirectional"))
    )
    (net (code "21") (name "EZFET_UARTRXD") (class "Default")
      (node (ref "JP6.1") (pin "1") (pinfunction "1_1") (pintype "passive"))
      (node (ref "MSP101") (pin "38") (pinfunction "38_38") (pintype "bidirectional"))
    )
    (net (code "22") (name "EZFET_UARTTXD") (class "Default")
      (node (ref "JP6.2") (pin "1") (pinfunction "1_1") (pintype "passive"))
      (node (ref "MSP101") (pin "37") (pinfunction "37_37") (pintype "bidirectional"))
    )
    (net (code "23") (name "EZFET_V18") (class "Default")
      (node (ref "C102") (pin "1") (pinfunction "1_1") (pintype "passive"))
      (node (ref "MSP101") (pin "55") (pinfunction "55_55") (pintype "power_in"))
    )
    (net (code "24") (name "EZFET_VBUS") (class "Default")
      (node (ref "C402") (pin "1") (pinfunction "1_1") (pintype "passive"))
      (node (ref "C403") (pin "+") (pinfunction "+_+") (pintype "passive"))
      (node (ref "C404") (pin "2") (pinfunction "2_2") (pintype "passive"))
      (node (ref "J401") (pin "VBUS") (pinfunction "VBUS_VBUS") (pintype "input"))
      (node (ref "JP1") (pin "1") (pinfunction "1_1") (pintype "passive"))
      (node (ref "MSP101") (pin "53") (pinfunction "53_53") (pintype "power_in"))
      (node (ref "R124") (pin "1") (pinfunction "1_1") (pintype "passive"))
      (node (ref "U402") (pin "3") (pinfunction "VIN_3") (pintype "power_in"))
      (node (ref "U402") (pin "5") (pinfunction "EN_5") (pintype "input"))
      (node (ref "U404") (pin "1") (pinfunction "VCC_1") (pintype "power_in"))
    )
    (net (code "25") (name "EZFET_VCC") (class "Default")
      (node (ref "C103") (pin "1") (pinfunction "1_1") (pintype "passive"))
      (node (ref "C104") (pin "+") (pinfunction "+_+") (pintype "passive"))
      (node (ref "C113") (pin "1") (pinfunction "1_1") (pintype "passive"))
      (node (ref "C401") (pin "2") (pinfunction "2_2") (pintype "passive"))
      (node (ref "C407") (pin "1") (pinfunction "1_1") (pintype "passive"))
      (node (ref "IC401") (pin "25") (pinfunction "VCC_25") (pintype "power_in"))
      (node (ref "IC401") (pin "26") (pinfunction "~{EXTMEM}_26") (pintype "input"))
      (node (ref "IC401") (pin "3") (pinfunction "VCC_3") (pintype "power_in"))
      (node (ref "IC401") (pin "6") (pinfunction "EEDATA/GANGED_6") (pintype "bidirectional"))
      (node (ref "IC401") (pin "8") (pinfunction "BUSPWR_8") (pintype "input"))
      (node (ref "JP2") (pin "1") (pinfunction "1_1") (pintype "passive"))
      (node (ref "L401") (pin "P$2") (pinfunction "2_P$2") (pintype "passive"))
      (node (ref "MSP101") (pin "11") (pinfunction "11_11") (pintype "power_in"))
      (node (ref "MSP101") (pin "15") (pinfunction "15_15") (pintype "power_in"))
      (node (ref "MSP101") (pin "40") (pinfunction "40_40") (pintype "power_in"))
      (node (ref "R109") (pin "2") (pinfunction "2_2") (pintype "passive"))
      (node (ref "R121") (pin "1") (pinfunction "1_1") (pintype "passive"))
      (node (ref "R402") (pin "1") (pinfunction "1_1") (pintype "passive"))
      (node (ref "R403") (pin "1") (pinfunction "1_1") (pintype "passive"))
      (node (ref "R404") (pin "1") (pinfunction "1_1") (pintype "passive"))
      (node (ref "U402") (pin "6") (pinfunction "FB_6") (pintype "input"))
    )
    (net (code "26") (name "EZFET_VREF") (class "Default")
      (node (ref "C121") (pin "1") (pinfunction "1_1") (pintype "passive"))
      (node (ref "MSP101") (pin "9") (pinfunction "9_9") (pintype "bidirectional"))
    )
    (net (code "27") (name "EZFET_VUSB") (class "Default")
      (node (ref "C107") (pin "1") (pinfunction "1_1") (pintype "passive"))
      (node (ref "MSP101") (pin "54") (pinfunction "54_54") (pintype "power_in"))
    )
    (net (code "28") (name "EZFET_XT2IN") (class "Default")
      (node (ref "MSP101") (pin "57") (pinfunction "57_57") (pintype "bidirectional"))
      (node (ref "Q101") (pin "1") (pinfunction "1_1") (pintype "passive"))
    )
    (net (code "29") (name "EZFET_XT2OUT") (class "Default")
      (node (ref "MSP101") (pin "58") (pinfunction "58_58") (pintype "bidirectional"))
      (node (ref "Q101") (pin "3") (pinfunction "3_3") (pintype "passive"))
    )
    (net (code "30") (name "GND") (class "Default")
      (node (ref "C101") (pin "2") (pinfunction "2_2") (pintype "passive"))
      (node (ref "C102") (pin "2") (pinfunction "2_2") (pintype "passive"))
      (node (ref "C103") (pin "2") (pinfunction "2_2") (pintype "passive"))
      (node (ref "C104") (pin "-") (pinfunction "-_-") (pintype "passive"))
      (node (ref "C107") (pin "2") (pinfunction "2_2") (pintype "passive"))
      (node (ref "C110") (pin "2") (pinfunction "2_2") (pintype "passive"))
      (node (ref "C111") (pin "2") (pinfunction "2_2") (pintype "passive"))
      (node (ref "C112") (pin "2") (pinfunction "2_2") (pintype "passive"))
      (node (ref "C113") (pin "2") (pinfunction "2_2") (pintype "passive"))
      (node (ref "C121") (pin "2") (pinfunction "2_2") (pintype "passive"))
      (node (ref "C122") (pin "1") (pinfunction "1_1") (pintype "passive"))
      (node (ref "C123") (pin "1") (pinfunction "1_1") (pintype "passive"))
      (node (ref "C14") (pin "2") (pinfunction "2_2") (pintype "passive"))
      (node (ref "C15") (pin "2") (pinfunction "2_2") (pintype "passive"))
      (node (ref "C16") (pin "2") (pinfunction "2_2") (pintype "passive"))
      (node (ref "C17") (pin "2") (pinfunction "2_2") (pintype "passive"))
      (node (ref "C18") (pin "1") (pinfunction "1_1") (pintype "passive"))
      (node (ref "C19") (pin "1") (pinfunction "1_1") (pintype "passive"))
      (node (ref "C20") (pin "2") (pinfunction "2_2") (pintype "passive"))
      (node (ref "C21") (pin "2") (pinfunction "2_2") (pintype "passive"))
      (node (ref "C23") (pin "2") (pinfunction "2_2") (pintype "passive"))
      (node (ref "C24") (pin "2") (pinfunction "2_2") (pintype "passive"))
      (node (ref "C25") (pin "1") (pinfunction "1_1") (pintype "passive"))
      (node (ref "C26") (pin "1") (pinfunction "1_1") (pintype "passive"))
      (node (ref "C27") (pin "-") (pinfunction "-_-") (pintype "passive"))
      (node (ref "C28") (pin "1") (pinfunction "1_1") (pintype "passive"))
      (node (ref "C29") (pin "2") (pinfunction "2_2") (pintype "passive"))
      (node (ref "C30") (pin "-") (pinfunction "-_-") (pintype "passive"))
      (node (ref "C31") (pin "1") (pinfunction "1_1") (pintype "passive"))
      (node (ref "C401") (pin "1") (pinfunction "1_1") (pintype "passive"))
      (node (ref "C402") (pin "2") (pinfunction "2_2") (pintype "passive"))
      (node (ref "C403") (pin "-") (pinfunction "-_-") (pintype "passive"))
      (node (ref "C404") (pin "1") (pinfunction "1_1") (pintype "passive"))
      (node (ref "C405") (pin "2") (pinfunction "2_2") (pintype "passive"))
      (node (ref "C406") (pin "2") (pinfunction "2_2") (pintype "passive"))
      (node (ref "C407") (pin "2") (pinfunction "2_2") (pintype "passive"))
      (node (ref "C408") (pin "2") (pinfunction "2_2") (pintype "passive"))
      (node (ref "C409") (pin "2") (pinfunction "2_2") (pintype "passive"))
      (node (ref "C410") (pin "2") (pinfunction "2_2") (pintype "passive"))
      (node (ref "C411") (pin "2") (pinfunction "2_2") (pintype "passive"))
      (node (ref "C412") (pin "2") (pinfunction "2_2") (pintype "passive"))
      (node (ref "IC401") (pin "27") (pinfunction "TSTPLL/48MCLK_27") (pintype "bidirectional"))
      (node (ref "IC401") (pin "28") (pinfunction "GND_28") (pintype "power_in"))
      (node (ref "IC401") (pin "31") (pinfunction "TSTMODE_31") (pintype "input"))
      (node (ref "IC401") (pin "7") (pinfunction "GND_7") (pintype "power_in"))
      (node (ref "J1") (pin "4") (pinfunction "4_4") (pintype "passive"))
      (node (ref "J10") (pin "1") (pinfunction "1_1") (pintype "passive"))
      (node (ref "J10") (pin "2") (pinfunction "2_2") (pintype "passive"))
      (node (ref "J3") (pin "1") (pinfunction "1_1") (pintype "passive"))
      (node (ref "J3") (pin "2") (pinfunction "2_2") (pintype "passive"))
      (node (ref "J401") (pin "GND") (pinfunction "GND_GND") (pintype "input"))
      (node (ref "J5") (pin "2") (pinfunction "2_2") (pintype "passive"))
      (node (ref "JP3") (pin "1") (pinfunction "1_1") (pintype "passive"))
      (node (ref "JP3") (pin "2") (pinfunction "2_2") (pintype "passive"))
      (node (ref "LED1") (pin "C") (pinfunction "C_C") (pintype "passive"))
      (node (ref "LED101") (pin "C") (pinfunction "C_C") (pintype "passive"))
      (node (ref "LED102") (pin "C") (pinfunction "C_C") (pintype "passive"))
      (node (ref "LED2") (pin "C") (pinfunction "C_C") (pintype "passive"))
      (node (ref "MSP101") (pin "14") (pinfunction "14_14") (pintype "power_in"))
      (node (ref "MSP101") (pin "16") (pinfunction "16_16") (pintype "power_in"))
      (node (ref "MSP101") (pin "39") (pinfunction "39_39") (pintype "power_in"))
      (node (ref "MSP101") (pin "49") (pinfunction "49_49") (pintype "power_in"))
      (node (ref "MSP101") (pin "56") (pinfunction "56_56") (pintype "power_in"))
      (node (ref "MSP101") (pin "TP") (pinfunction "TP_TP") (pintype "power_in"))
      (node (ref "Q101") (pin "2") (pinfunction "2_2") (pintype "passive"))
      (node (ref "Q2") (pin "P3") (pinfunction "GND_P3") (pintype "power_in"))
      (node (ref "Q4") (pin "2") (pinfunction "2_2") (pintype "passive"))
      (node (ref "Q401") (pin "2") (pinfunction "2_2") (pintype "passive"))
      (node (ref "R106") (pin "1") (pinfunction "1_1") (pintype "passive"))
      (node (ref "R122") (pin "2") (pinfunction "2_2") (pintype "passive"))
      (node (ref "R125") (pin "2") (pinfunction "2_2") (pintype "passive"))
      (node (ref "R16") (pin "1") (pinfunction "1_1") (pintype "passive"))
      (node (ref "R401") (pin "2") (pinfunction "2_2") (pintype "passive"))
      (node (ref "R408") (pin "1") (pinfunction "1_1") (pintype "passive"))
      (node (ref "R409") (pin "1") (pinfunction "1_1") (pintype "passive"))
      (node (ref "R412") (pin "1") (pinfunction "1_1") (pintype "passive"))
      (node (ref "R413") (pin "1") (pinfunction "1_1") (pintype "passive"))
      (node (ref "R414") (pin "2") (pinfunction "2_2") (pintype "passive"))
      (node (ref "R415") (pin "2") (pinfunction "2_2") (pintype "passive"))
      (node (ref "R418") (pin "2") (pinfunction "2_2") (pintype "passive"))
      (node (ref "R419") (pin "2") (pinfunction "2_2") (pintype "passive"))
      (node (ref "S1") (pin "2") (pinfunction "S_2") (pintype "passive"))
      (node (ref "S2") (pin "2") (pinfunction "S_2") (pintype "passive"))
      (node (ref "S3") (pin "1") (pinfunction "P_1") (pintype "passive"))
      (node (ref "TP104") (pin "1") (pinfunction "1_1") (pintype "passive"))
      (node (ref "U402") (pin "1") (pinfunction "MODE_1") (pintype "input"))
      (node (ref "U402") (pin "4") (pinfunction "GND_4") (pintype "power_in"))
      (node (ref "U404") (pin "4") (pinfunction "GND_4") (pintype "power_in"))
      (node (ref "U6") (pin "14") (pinfunction "14_14") (pintype "power_in"))
      (node (ref "U6") (pin "19") (pinfunction "19_19") (pintype "power_in"))
      (node (ref "U6") (pin "49") (pinfunction "49_49") (pintype "power_in"))
      (node (ref "U6") (pin "61") (pinfunction "61_61") (pintype "power_in"))
      (node (ref "U6") (pin "68") (pinfunction "68_68") (pintype "power_in"))
    )
    (net (code "31") (name "HUB_DM1") (class "Default")
      (node (ref "R31") (pin "1") (pinfunction "1_1") (pintype "passive"))
      (node (ref "R416") (pin "2") (pinfunction "2_2") (pintype "passive"))
      (node (ref "R419") (pin "1") (pinfunction "1_1") (pintype "passive"))
    )
    (net (code "32") (name "HUB_DM2") (class "Default")
      (node (ref "R103") (pin "1") (pinfunction "1_1") (pintype "passive"))
      (node (ref "R410") (pin "2") (pinfunction "2_2") (pintype "passive"))
      (node (ref "R415") (pin "1") (pinfunction "1_1") (pintype "passive"))
    )
    (net (code "33") (name "HUB_DP1") (class "Default")
      (node (ref "R32") (pin "1") (pinfunction "1_1") (pintype "passive"))
      (node (ref "R417") (pin "2") (pinfunction "2_2") (pintype "passive"))
      (node (ref "R418") (pin "1") (pinfunction "1_1") (pintype "passive"))
    )
    (net (code "34") (name "HUB_DP2") (class "Default")
      (node (ref "R104") (pin "1") (pinfunction "1_1") (pintype "passive"))
      (node (ref "R411") (pin "2") (pinfunction "2_2") (pintype "passive"))
      (node (ref "R414") (pin "1") (pinfunction "1_1") (pintype "passive"))
    )
    (net (code "35") (name "Net-(C15-Pad1)") (class "Default")
      (node (ref "C15") (pin "1") (pinfunction "1_1") (pintype "passive"))
      (node (ref "U6") (pin "67") (pinfunction "67_67") (pintype "power_in"))
    )
    (net (code "36") (name "Net-(C16-Pad1)") (class "Default")
      (node (ref "C16") (pin "1") (pinfunction "1_1") (pintype "passive"))
      (node (ref "U6") (pin "66") (pinfunction "66_66") (pintype "power_in"))
    )
    (net (code "37") (name "Net-(C18-Pad2)") (class "Default")
      (node (ref "C18") (pin "2") (pinfunction "2_2") (pintype "passive"))
      (node (ref "U6") (pin "20") (pinfunction "20_20") (pintype "power_in"))
    )
    (net (code "38") (name "Net-(C29-Pad1)") (class "Default")
      (node (ref "C29") (pin "1") (pinfunction "1_1") (pintype "passive"))
      (node (ref "R28") (pin "1") (pinfunction "1_1") (pintype "passive"))
      (node (ref "U6") (pin "11") (pinfunction "11_11") (pintype "power_in"))
    )
    (net (code "39") (name "Net-(C101-Pad1)") (class "Default")
      (node (ref "C101") (pin "1") (pinfunction "1_1") (pintype "passive"))
      (node (ref "MSP101") (pin "17") (pinfunction "17_17") (pintype "power_in"))
    )
    (net (code "40") (name "Net-(IC401-DM0)") (class "Default")
      (node (ref "C406") (pin "1") (pinfunction "1_1") (pintype "passive"))
      (node (ref "IC401") (pin "2") (pinfunction "DM0_2") (pintype "bidirectional"))
      (node (ref "R406") (pin "1") (pinfunction "1_1") (pintype "passive"))
    )
    (net (code "41") (name "Net-(IC401-DM1)") (class "Default")
      (node (ref "C412") (pin "1") (pinfunction "1_1") (pintype "passive"))
      (node (ref "IC401") (pin "11") (pinfunction "DM1_11") (pintype "bidirectional"))
      (node (ref "R416") (pin "1") (pinfunction "1_1") (pintype "passive"))
    )
    (net (code "42") (name "Net-(IC401-DM2)") (class "Default")
      (node (ref "C410") (pin "1") (pinfunction "1_1") (pintype "passive"))
      (node (ref "IC401") (pin "15") (pinfunction "DM2_15") (pintype "bidirectional"))
      (node (ref "R410") (pin "1") (pinfunction "1_1") (pintype "passive"))
    )
    (net (code "43") (name "Net-(IC401-DM3)") (class "Default")
      (node (ref "IC401") (pin "19") (pinfunction "DM3_19") (pintype "bidirectional"))
      (node (ref "R413") (pin "2") (pinfunction "2_2") (pintype "passive"))
    )
    (net (code "44") (name "Net-(IC401-DM4)") (class "Default")
      (node (ref "IC401") (pin "23") (pinfunction "DM4_23") (pintype "bidirectional"))
      (node (ref "R409") (pin "2") (pinfunction "2_2") (pintype "passive"))
    )
    (net (code "45") (name "Net-(IC401-DP0)") (class "Default")
      (node (ref "C405") (pin "1") (pinfunction "1_1") (pintype "passive"))
      (node (ref "IC401") (pin "1") (pinfunction "DP0_1") (pintype "bidirectional"))
      (node (ref "R403") (pin "2") (pinfunction "2_2") (pintype "passive"))
      (node (ref "R405") (pin "1") (pinfunction "1_1") (pintype "passive"))
    )
    (net (code "46") (name "Net-(IC401-DP1)") (class "Default")
      (node (ref "C411") (pin "1") (pinfunction "1_1") (pintype "passive"))
      (node (ref "IC401") (pin "12") (pinfunction "DP1_12") (pintype "bidirectional"))
      (node (ref "R417") (pin "1") (pinfunction "1_1") (pintype "passive"))
    )
    (net (code "47") (name "Net-(IC401-DP2)") (class "Default")
      (node (ref "C409") (pin "1") (pinfunction "1_1") (pintype "passive"))
      (node (ref "IC401") (pin "16") (pinfunction "DP2_16") (pintype "bidirectional"))
      (node (ref "R411") (pin "1") (pinfunction "1_1") (pintype "passive"))
    )
    (net (code "48") (name "Net-(IC401-DP3)") (class "Default")
      (node (ref "IC401") (pin "20") (pinfunction "DP3_20") (pintype "bidirectional"))
      (node (ref "R412") (pin "2") (pinfunction "2_2") (pintype "passive"))
    )
    (net (code "49") (name "Net-(IC401-DP4)") (class "Default")
      (node (ref "IC401") (pin "24") (pinfunction "DP4_24") (pintype "bidirectional"))
      (node (ref "R408") (pin "2") (pinfunction "2_2") (pintype "passive"))
    )
    (net (code "50") (name "Net-(IC401-XTAL1)") (class "Default")
      (node (ref "IC401") (pin "30") (pinfunction "XTAL1_30") (pintype "input"))
      (node (ref "Q401") (pin "1") (pinfunction "1_1") (pintype "passive"))
    )
    (net (code "51") (name "Net-(IC401-XTAL2)") (class "Default")
      (node (ref "IC401") (pin "29") (pinfunction "XTAL2_29") (pintype "output"))
      (node (ref "R407") (pin "2") (pinfunction "2_2") (pintype "passive"))
    )
    (net (code "52") (name "Net-(IC401-~{RESET})") (class "Default")
      (node (ref "C408") (pin "1") (pinfunction "1_1") (pintype "passive"))
      (node (ref "IC401") (pin "4") (pinfunction "~{RESET}_4") (pintype "input"))
      (node (ref "R404") (pin "2") (pinfunction "2_2") (pintype "passive"))
    )
    (net (code "53") (name "Net-(J401-PadSHIELD1)") (class "Default")
      (node (ref "J401") (pin "SHIELD1") (pinfunction "SHIELD1_SHIELD1") (pintype "bidirectional"))
      (node (ref "R401") (pin "1") (pinfunction "1_1") (pintype "passive"))
    )
    (net (code "54") (name "Net-(JP8-Pad2)") (class "Default")
      (node (ref "JP8") (pin "2") (pinfunction "2_2") (pintype "passive"))
      (node (ref "R29") (pin "1") (pinfunction "1_1") (pintype "passive"))
    )
    (net (code "55") (name "Net-(L401-1)") (class "Default")
      (node (ref "L401") (pin "P$1") (pinfunction "1_P$1") (pintype "passive"))
      (node (ref "U402") (pin "2") (pinfunction "SW_2") (pintype "output"))
    )
    (net (code "56") (name "Net-(LED1-PadA)") (class "Default")
      (node (ref "LED1") (pin "A") (pinfunction "A_A") (pintype "passive"))
      (node (ref "R29") (pin "2") (pinfunction "2_2") (pintype "passive"))
    )
    (net (code "57") (name "Net-(LED2-PadA)") (class "Default")
      (node (ref "LED2") (pin "A") (pinfunction "A_A") (pintype "passive"))
      (node (ref "R30") (pin "2") (pinfunction "2_2") (pintype "passive"))
    )
    (net (code "58") (name "Net-(LED101-PadA)") (class "Default")
      (node (ref "LED101") (pin "A") (pinfunction "A_A") (pintype "passive"))
      (node (ref "R101") (pin "1") (pinfunction "1_1") (pintype "passive"))
    )
    (net (code "59") (name "Net-(LED102-PadA)") (class "Default")
      (node (ref "LED102") (pin "A") (pinfunction "A_A") (pintype "passive"))
      (node (ref "R102") (pin "1") (pinfunction "1_1") (pintype "passive"))
    )
    (net (code "60") (name "Net-(Q2-1)") (class "Default")
      (node (ref "C25") (pin "2") (pinfunction "2_2") (pintype "passive"))
      (node (ref "Q2") (pin "P1") (pinfunction "1_P1") (pintype "bidirectional"))
      (node (ref "U6") (pin "13") (pinfunction "13_13") (pintype "bidirectional"))
    )
    (net (code "61") (name "Net-(Q2-2)") (class "Default")
      (node (ref "C26") (pin "2") (pinfunction "2_2") (pintype "passive"))
      (node (ref "Q2") (pin "P2") (pinfunction "2_P2") (pintype "bidirectional"))
      (node (ref "U6") (pin "12") (pinfunction "12_12") (pintype "bidirectional"))
    )
    (net (code "62") (name "Net-(Q4-Pad1)") (class "Default")
      (node (ref "Q4") (pin "1") (pinfunction "1_1") (pintype "passive"))
      (node (ref "U6") (pin "70") (pinfunction "70_70") (pintype "bidirectional"))
    )
    (net (code "63") (name "Net-(Q4-Pad3)") (class "Default")
      (node (ref "Q4") (pin "3") (pinfunction "3_3") (pintype "passive"))
      (node (ref "U6") (pin "69") (pinfunction "69_69") (pintype "bidirectional"))
    )
    (net (code "64") (name "Net-(Q401-Pad3)") (class "Default")
      (node (ref "Q401") (pin "3") (pinfunction "3_3") (pintype "passive"))
      (node (ref "R407") (pin "1") (pinfunction "1_1") (pintype "passive"))
    )
    (net (code "65") (name "Net-(S5-S)") (class "Default")
      (node (ref "R14") (pin "1") (pinfunction "1_1") (pintype "passive"))
      (node (ref "S5") (pin "2") (pinfunction "S_2") (pintype "passive"))
    )
    (net (code "66") (name "Net-(U404-IO1)") (class "Default")
      (node (ref "J401") (pin "D-") (pinfunction "D-_D-") (pintype "input"))
      (node (ref "R406") (pin "2") (pinfunction "2_2") (pintype "passive"))
      (node (ref "U404") (pin "3") (pinfunction "IO1_3") (pintype "bidirectional"))
    )
    (net (code "67") (name "Net-(U404-IO2)") (class "Default")
      (node (ref "J401") (pin "D+") (pinfunction "D+_D+") (pintype "input"))
      (node (ref "R405") (pin "2") (pinfunction "2_2") (pintype "passive"))
      (node (ref "U404") (pin "5") (pinfunction "IO2_5") (pintype "bidirectional"))
    )
    (net (code "68") (name "P1.0") (class "Default")
      (node (ref "JP8") (pin "1") (pinfunction "1_1") (pintype "passive"))
      (node (ref "U6") (pin "21") (pinfunction "21_21") (pintype "bidirectional"))
    )
    (net (code "69") (name "P1.1") (class "Default")
      (node (ref "S2") (pin "1") (pinfunction "P_1") (pintype "passive"))
      (node (ref "U6") (pin "22") (pinfunction "22_22") (pintype "bidirectional"))
    )
    (net (code "70") (name "P1.2") (class "Default")
      (node (ref "J5") (pin "11") (pinfunction "11_11") (pintype "passive"))
      (node (ref "U6") (pin "23") (pinfunction "23_23") (pintype "bidirectional"))
    )
    (net (code "71") (name "P1.3") (class "Default")
      (node (ref "J5") (pin "9") (pinfunction "9_9") (pintype "passive"))
      (node (ref "U6") (pin "24") (pinfunction "24_24") (pintype "bidirectional"))
    )
    (net (code "72") (name "P1.4") (class "Default")
      (node (ref "J5") (pin "7") (pinfunction "7_7") (pintype "passive"))
      (node (ref "U6") (pin "25") (pinfunction "25_25") (pintype "bidirectional"))
    )
    (net (code "73") (name "P1.5") (class "Default")
      (node (ref "J5") (pin "5") (pinfunction "5_5") (pintype "passive"))
      (node (ref "U6") (pin "26") (pinfunction "26_26") (pintype "bidirectional"))
    )
    (net (code "74") (name "P1.6") (class "Default")
      (node (ref "J1") (pin "9") (pinfunction "9_9") (pintype "passive"))
      (node (ref "U6") (pin "27") (pinfunction "27_27") (pintype "bidirectional"))
    )
    (net (code "75") (name "P1.7") (class "Default")
      (node (ref "JP6.3") (pin "2") (pinfunction "2_2") (pintype "passive"))
      (node (ref "U6") (pin "28") (pinfunction "28_28") (pintype "bidirectional"))
    )
    (net (code "76") (name "P2.0") (class "Default")
      (node (ref "J5") (pin "4") (pinfunction "4_4") (pintype "passive"))
      (node (ref "U6") (pin "29") (pinfunction "29_29") (pintype "bidirectional"))
    )
    (net (code "77") (name "P2.1") (class "Default")
      (node (ref "S1") (pin "1") (pinfunction "P_1") (pintype "passive"))
      (node (ref "U6") (pin "30") (pinfunction "30_30") (pintype "bidirectional"))
    )
    (net (code "78") (name "P2.2") (class "Default")
      (node (ref "J5") (pin "6") (pinfunction "6_6") (pintype "passive"))
      (node (ref "U6") (pin "31") (pinfunction "31_31") (pintype "bidirectional"))
    )
    (net (code "79") (name "P2.3") (class "Default")
      (node (ref "J5") (pin "18") (pinfunction "18_18") (pintype "passive"))
      (node (ref "U6") (pin "32") (pinfunction "32_32") (pintype "bidirectional"))
    )
    (net (code "80") (name "P2.4") (class "Default")
      (node (ref "J5") (pin "3") (pinfunction "3_3") (pintype "passive"))
      (node (ref "U6") (pin "33") (pinfunction "33_33") (pintype "bidirectional"))
    )
    (net (code "81") (name "P2.5") (class "Default")
      (node (ref "J5") (pin "1") (pinfunction "1_1") (pintype "passive"))
      (node (ref "U6") (pin "34") (pinfunction "34_34") (pintype "bidirectional"))
    )
    (net (code "82") (name "P2.6") (class "Default")
      (node (ref "J5") (pin "16") (pinfunction "16_16") (pintype "passive"))
      (node (ref "U6") (pin "35") (pinfunction "35_35") (pintype "bidirectional"))
    )
    (net (code "83") (name "P2.7") (class "Default")
      (node (ref "J1") (pin "15") (pinfunction "15_15") (pintype "passive"))
      (node (ref "U6") (pin "36") (pinfunction "36_36") (pintype "bidirectional"))
    )
    (net (code "84") (name "P3.0") (class "Default")
      (node (ref "J5") (pin "12") (pinfunction "12_12") (pintype "passive"))
      (node (ref "U6") (pin "37") (pinfunction "37_37") (pintype "bidirectional"))
    )
    (net (code "85") (name "P3.1") (class "Default")
      (node (ref "J5") (pin "14") (pinfunction "14_14") (pintype "passive"))
      (node (ref "U6") (pin "38") (pinfunction "38_38") (pintype "bidirectional"))
    )
    (net (code "86") (name "P3.2") (class "Default")
      (node (ref "J1") (pin "13") (pinfunction "13_13") (pintype "passive"))
      (node (ref "U6") (pin "39") (pinfunction "39_39") (pintype "bidirectional"))
    )
    (net (code "87") (name "P3.3") (class "Default")
      (node (ref "J1") (pin "7") (pinfunction "7_7") (pintype "passive"))
      (node (ref "U6") (pin "40") (pinfunction "40_40") (pintype "bidirectional"))
    )
    (net (code "88") (name "P3.4") (class "Default")
      (node (ref "J1") (pin "5") (pinfunction "5_5") (pintype "passive"))
      (node (ref "U6") (pin "41") (pinfunction "41_41") (pintype "bidirectional"))
    )
    (net (code "89") (name "P3.5") (class "Default")
      (node (ref "J1") (pin "20") (pinfunction "20_20") (pintype "passive"))
      (node (ref "U6") (pin "42") (pinfunction "42_42") (pintype "bidirectional"))
    )
    (net (code "90") (name "P3.6") (class "Default")
      (node (ref "J1") (pin "18") (pinfunction "18_18") (pintype "passive"))
      (node (ref "U6") (pin "43") (pinfunction "43_43") (pintype "bidirectional"))
    )
    (net (code "91") (name "P3.7") (class "Default")
      (node (ref "J5") (pin "17") (pinfunction "17_17") (pintype "passive"))
      (node (ref "U6") (pin "44") (pinfunction "44_44") (pintype "bidirectional"))
    )
    (net (code "92") (name "P4.0") (class "Default")
      (node (ref "J5") (pin "15") (pinfunction "15_15") (pintype "passive"))
      (node (ref "U6") (pin "45") (pinfunction "45_45") (pintype "bidirectional"))
    )
    (net (code "93") (name "P4.1") (class "Default")
      (node (ref "J1") (pin "19") (pinfunction "19_19") (pintype "passive"))
      (node (ref "U6") (pin "46") (pinfunction "46_46") (pintype "bidirectional"))
    )
    (net (code "94") (name "P4.2") (class "Default")
      (node (ref "J1") (pin "17") (pinfunction "17_17") (pintype "passive"))
      (node (ref "U6") (pin "47") (pinfunction "47_47") (pintype "bidirectional"))
    )
    (net (code "95") (name "P4.3") (class "Default")
      (node (ref "J5") (pin "13") (pinfunction "13_13") (pintype "passive"))
      (node (ref "U6") (pin "48") (pinfunction "48_48") (pintype "bidirectional"))
    )
    (net (code "96") (name "P4.4{slash}UCA1TXD") (class "Default")
      (node (ref "JP6.1") (pin "2") (pinfunction "2_2") (pintype "passive"))
      (node (ref "U6") (pin "51") (pinfunction "51_51") (pintype "bidirectional"))
    )
    (net (code "97") (name "P4.5{slash}UCA1RXD") (class "Default")
      (node (ref "JP6.2") (pin "2") (pinfunction "2_2") (pintype "passive"))
      (node (ref "U6") (pin "52") (pinfunction "52_52") (pintype "bidirectional"))
    )
    (net (code "98") (name "P4.7") (class "Default")
      (node (ref "R30") (pin "1") (pinfunction "1_1") (pintype "passive"))
      (node (ref "U6") (pin "54") (pinfunction "54_54") (pintype "bidirectional"))
    )
    (net (code "99") (name "P6.0") (class "Default")
      (node (ref "J1") (pin "6") (pinfunction "6_6") (pintype "passive"))
      (node (ref "U6") (pin "77") (pinfunction "77_77") (pintype "bidirectional"))
    )
    (net (code "100") (name "P6.1") (class "Default")
      (node (ref "J1") (pin "8") (pinfunction "8_8") (pintype "passive"))
      (node (ref "U6") (pin "78") (pinfunction "78_78") (pintype "bidirectional"))
    )
    (net (code "101") (name "P6.2") (class "Default")
      (node (ref "J1") (pin "10") (pinfunction "10_10") (pintype "passive"))
      (node (ref "U6") (pin "79") (pinfunction "79_79") (pintype "bidirectional"))
    )
    (net (code "102") (name "P6.3") (class "Default")
      (node (ref "J1") (pin "12") (pinfunction "12_12") (pintype "passive"))
      (node (ref "U6") (pin "80") (pinfunction "80_80") (pintype "bidirectional"))
    )
    (net (code "103") (name "P6.4") (class "Default")
      (node (ref "J1") (pin "14") (pinfunction "14_14") (pintype "passive"))
      (node (ref "U6") (pin "1") (pinfunction "1_1") (pintype "bidirectional"))
    )
    (net (code "104") (name "P6.5") (class "Default")
      (node (ref "J1") (pin "3") (pinfunction "3_3") (pintype "passive"))
      (node (ref "U6") (pin "2") (pinfunction "2_2") (pintype "bidirectional"))
    )
    (net (code "105") (name "P6.6") (class "Default")
      (node (ref "J1") (pin "11") (pinfunction "11_11") (pintype "passive"))
      (node (ref "U6") (pin "3") (pinfunction "3_3") (pintype "bidirectional"))
    )
    (net (code "106") (name "P6.7") (class "Default")
      (node (ref "JP6.4") (pin "2") (pinfunction "2_2") (pintype "passive"))
      (node (ref "U6") (pin "4") (pinfunction "4_4") (pintype "bidirectional"))
    )
    (net (code "107") (name "P7.0") (class "Default")
      (node (ref "J1") (pin "16") (pinfunction "16_16") (pintype "passive"))
      (node (ref "U6") (pin "5") (pinfunction "5_5") (pintype "bidirectional"))
    )
    (net (code "108") (name "P7.4") (class "Default")
      (node (ref "J5") (pin "8") (pinfunction "8_8") (pintype "passive"))
      (node (ref "U6") (pin "57") (pinfunction "57_57") (pintype "bidirectional"))
    )
    (net (code "109") (name "P8.1") (class "Default")
      (node (ref "J5") (pin "20") (pinfunction "20_20") (pintype "passive"))
      (node (ref "U6") (pin "16") (pinfunction "16_16") (pintype "bidirectional"))
    )
    (net (code "110") (name "P8.2") (class "Default")
      (node (ref "J5") (pin "19") (pinfunction "19_19") (pintype "passive"))
      (node (ref "U6") (pin "17") (pinfunction "17_17") (pintype "bidirectional"))
    )
    (net (code "111") (name "RST{slash}SBWTDIO") (class "Default")
      (node (ref "C17") (pin "1") (pinfunction "1_1") (pintype "passive"))
      (node (ref "J5") (pin "10") (pinfunction "10_10") (pintype "passive"))
      (node (ref "JP4.2") (pin "2") (pinfunction "2_2") (pintype "passive"))
      (node (ref "R27") (pin "1") (pinfunction "1_1") (pintype "passive"))
      (node (ref "S3") (pin "2") (pinfunction "S_2") (pintype "passive"))
      (node (ref "U6") (pin "76") (pinfunction "76_76") (pintype "bidirectional"))
    )
    (net (code "112") (name "TARGET_DM") (class "Default")
      (node (ref "C24") (pin "1") (pinfunction "1_1") (pintype "passive"))
      (node (ref "R31") (pin "2") (pinfunction "2_2") (pintype "passive"))
      (node (ref "U6") (pin "64") (pinfunction "64_64") (pintype "bidirectional"))
    )
    (net (code "113") (name "TARGET_DP") (class "Default")
      (node (ref "C23") (pin "1") (pinfunction "1_1") (pintype "passive"))
      (node (ref "R15") (pin "2") (pinfunction "2_2") (pintype "passive"))
      (node (ref "R32") (pin "2") (pinfunction "2_2") (pintype "passive"))
      (node (ref "U6") (pin "62") (pinfunction "62_62") (pintype "bidirectional"))
    )
    (net (code "114") (name "TARGET_PUR") (class "Default")
      (node (ref "R14") (pin "2") (pinfunction "2_2") (pintype "passive"))
      (node (ref "R15") (pin "1") (pinfunction "1_1") (pintype "passive"))
      (node (ref "R16") (pin "2") (pinfunction "2_2") (pintype "passive"))
      (node (ref "U6") (pin "63") (pinfunction "63_63") (pintype "bidirectional"))
    )
    (net (code "115") (name "TEST{slash}SBWTCK") (class "Default")
      (node (ref "JP4.1") (pin "2") (pinfunction "2_2") (pintype "passive"))
      (node (ref "U6") (pin "71") (pinfunction "71_71") (pintype "input"))
    )
    (net (code "116") (name "unconnected-(IC401-EECLK-Pad5)") (class "Default")
      (node (ref "IC401") (pin "5") (pinfunction "EECLK_5") (pintype "output"))
    )
    (net (code "117") (name "unconnected-(IC401-SUSPND-Pad32)") (class "Default")
      (node (ref "IC401") (pin "32") (pinfunction "SUSPND_32") (pintype "output"))
    )
    (net (code "118") (name "unconnected-(J401-PadNC)") (class "Default")
      (node (ref "J401") (pin "NC") (pinfunction "NC_NC") (pintype "input"))
    )
    (net (code "119") (name "unconnected-(J401-PadSHIELD2)") (class "Default")
      (node (ref "J401") (pin "SHIELD2") (pinfunction "SHIELD2_SHIELD2") (pintype "bidirectional"))
    )
    (net (code "120") (name "unconnected-(J401-PadSHIELD3)") (class "Default")
      (node (ref "J401") (pin "SHIELD3") (pinfunction "SHIELD3_SHIELD3") (pintype "bidirectional"))
    )
    (net (code "121") (name "unconnected-(J401-PadSHIELD4)") (class "Default")
      (node (ref "J401") (pin "SHIELD4") (pinfunction "SHIELD4_SHIELD4") (pintype "bidirectional"))
    )
    (net (code "122") (name "unconnected-(J401-PadSHIELD5)") (class "Default")
      (node (ref "J401") (pin "SHIELD5") (pinfunction "SHIELD5_SHIELD5") (pintype "bidirectional"))
    )
    (net (code "123") (name "unconnected-(J401-PadSHIELD6)") (class "Default")
      (node (ref "J401") (pin "SHIELD6") (pinfunction "SHIELD6_SHIELD6") (pintype "bidirectional"))
    )
    (net (code "124") (name "unconnected-(JP4.3-Pad2)") (class "Default")
      (node (ref "JP4.3") (pin "2") (pinfunction "2_2") (pintype "passive"))
    )
    (net (code "125") (name "unconnected-(MSP101-Pad3)") (class "Default")
      (node (ref "MSP101") (pin "3") (pinfunction "3_3") (pintype "bidirectional"))
    )
    (net (code "126") (name "unconnected-(MSP101-Pad4)") (class "Default")
      (node (ref "MSP101") (pin "4") (pinfunction "4_4") (pintype "bidirectional"))
    )
    (net (code "127") (name "unconnected-(MSP101-Pad5)") (class "Default")
      (node (ref "MSP101") (pin "5") (pinfunction "5_5") (pintype "bidirectional"))
    )
    (net (code "128") (name "unconnected-(MSP101-Pad6)") (class "Default")
      (node (ref "MSP101") (pin "6") (pinfunction "6_6") (pintype "bidirectional"))
    )
    (net (code "129") (name "unconnected-(MSP101-Pad7)") (class "Default")
      (node (ref "MSP101") (pin "7") (pinfunction "7_7") (pintype "bidirectional"))
    )
    (net (code "130") (name "unconnected-(MSP101-Pad8)") (class "Default")
      (node (ref "MSP101") (pin "8") (pinfunction "8_8") (pintype "bidirectional"))
    )
    (net (code "131") (name "unconnected-(MSP101-Pad10)") (class "Default")
      (node (ref "MSP101") (pin "10") (pinfunction "10_10") (pintype "bidirectional"))
    )
    (net (code "132") (name "unconnected-(MSP101-Pad12)") (class "Default")
      (node (ref "MSP101") (pin "12") (pinfunction "12_12") (pintype "bidirectional"))
    )
    (net (code "133") (name "unconnected-(MSP101-Pad13)") (class "Default")
      (node (ref "MSP101") (pin "13") (pinfunction "13_13") (pintype "bidirectional"))
    )
    (net (code "134") (name "unconnected-(MSP101-Pad18)") (class "Default")
      (node (ref "MSP101") (pin "18") (pinfunction "18_18") (pintype "bidirectional"))
    )
    (net (code "135") (name "unconnected-(MSP101-Pad19)") (class "Default")
      (node (ref "MSP101") (pin "19") (pinfunction "19_19") (pintype "bidirectional"))
    )
    (net (code "136") (name "unconnected-(MSP101-Pad22)") (class "Default")
      (node (ref "MSP101") (pin "22") (pinfunction "22_22") (pintype "bidirectional"))
    )
    (net (code "137") (name "unconnected-(MSP101-Pad23)") (class "Default")
      (node (ref "MSP101") (pin "23") (pinfunction "23_23") (pintype "bidirectional"))
    )
    (net (code "138") (name "unconnected-(MSP101-Pad24)") (class "Default")
      (node (ref "MSP101") (pin "24") (pinfunction "24_24") (pintype "bidirectional"))
    )
    (net (code "139") (name "unconnected-(MSP101-Pad25)") (class "Default")
      (node (ref "MSP101") (pin "25") (pinfunction "25_25") (pintype "bidirectional"))
    )
    (net (code "140") (name "unconnected-(MSP101-Pad26)") (class "Default")
      (node (ref "MSP101") (pin "26") (pinfunction "26_26") (pintype "bidirectional"))
    )
    (net (code "141") (name "unconnected-(MSP101-Pad27)") (class "Default")
      (node (ref "MSP101") (pin "27") (pinfunction "27_27") (pintype "bidirectional"))
    )
    (net (code "142") (name "unconnected-(MSP101-Pad28)") (class "Default")
      (node (ref "MSP101") (pin "28") (pinfunction "28_28") (pintype "bidirectional"))
    )
    (net (code "143") (name "unconnected-(MSP101-Pad29)") (class "Default")
      (node (ref "MSP101") (pin "29") (pinfunction "29_29") (pintype "bidirectional"))
    )
    (net (code "144") (name "unconnected-(MSP101-Pad30)") (class "Default")
      (node (ref "MSP101") (pin "30") (pinfunction "30_30") (pintype "bidirectional"))
    )
    (net (code "145") (name "unconnected-(MSP101-Pad31)") (class "Default")
      (node (ref "MSP101") (pin "31") (pinfunction "31_31") (pintype "bidirectional"))
    )
    (net (code "146") (name "unconnected-(MSP101-Pad34)") (class "Default")
      (node (ref "MSP101") (pin "34") (pinfunction "34_34") (pintype "bidirectional"))
    )
    (net (code "147") (name "unconnected-(MSP101-Pad35)") (class "Default")
      (node (ref "MSP101") (pin "35") (pinfunction "35_35") (pintype "bidirectional"))
    )
    (net (code "148") (name "unconnected-(MSP101-Pad36)") (class "Default")
      (node (ref "MSP101") (pin "36") (pinfunction "36_36") (pintype "bidirectional"))
    )
    (net (code "149") (name "unconnected-(MSP101-Pad41)") (class "Default")
      (node (ref "MSP101") (pin "41") (pinfunction "41_41") (pintype "bidirectional"))
    )
    (net (code "150") (name "unconnected-(MSP101-Pad42)") (class "Default")
      (node (ref "MSP101") (pin "42") (pinfunction "42_42") (pintype "bidirectional"))
    )
    (net (code "151") (name "unconnected-(MSP101-Pad46)") (class "Default")
      (node (ref "MSP101") (pin "46") (pinfunction "46_46") (pintype "bidirectional"))
    )
    (net (code "152") (name "unconnected-(MSP101-Pad47)") (class "Default")
      (node (ref "MSP101") (pin "47") (pinfunction "47_47") (pintype "bidirectional"))
    )
    (net (code "153") (name "unconnected-(MSP101-Pad48)") (class "Default")
      (node (ref "MSP101") (pin "48") (pinfunction "48_48") (pintype "bidirectional"))
    )
    (net (code "154") (name "unconnected-(U6-Pad6)") (class "Default")
      (node (ref "U6") (pin "6") (pinfunction "6_6") (pintype "bidirectional"))
    )
    (net (code "155") (name "unconnected-(U6-Pad7)") (class "Default")
      (node (ref "U6") (pin "7") (pinfunction "7_7") (pintype "bidirectional"))
    )
    (net (code "156") (name "unconnected-(U6-Pad8)") (class "Default")
      (node (ref "U6") (pin "8") (pinfunction "8_8") (pintype "bidirectional"))
    )
    (net (code "157") (name "unconnected-(U6-Pad9)") (class "Default")
      (node (ref "U6") (pin "9") (pinfunction "9_9") (pintype "bidirectional"))
    )
    (net (code "158") (name "unconnected-(U6-Pad10)") (class "Default")
      (node (ref "U6") (pin "10") (pinfunction "10_10") (pintype "bidirectional"))
    )
    (net (code "159") (name "unconnected-(U6-Pad15)") (class "Default")
      (node (ref "U6") (pin "15") (pinfunction "15_15") (pintype "bidirectional"))
    )
    (net (code "160") (name "unconnected-(U6-Pad53)") (class "Default")
      (node (ref "U6") (pin "53") (pinfunction "53_53") (pintype "bidirectional"))
    )
    (net (code "161") (name "unconnected-(U6-Pad55)") (class "Default")
      (node (ref "U6") (pin "55") (pinfunction "55_55") (pintype "bidirectional"))
    )
    (net (code "162") (name "unconnected-(U6-Pad56)") (class "Default")
      (node (ref "U6") (pin "56") (pinfunction "56_56") (pintype "bidirectional"))
    )
    (net (code "163") (name "unconnected-(U6-Pad58)") (class "Default")
      (node (ref "U6") (pin "58") (pinfunction "58_58") (pintype "bidirectional"))
    )
    (net (code "164") (name "unconnected-(U6-Pad59)") (class "Default")
      (node (ref "U6") (pin "59") (pinfunction "59_59") (pintype "bidirectional"))
    )
    (net (code "165") (name "unconnected-(U6-Pad60)") (class "Default")
      (node (ref "U6") (pin "60") (pinfunction "60_60") (pintype "bidirectional"))
    )
    (net (code "166") (name "unconnected-(U6-Pad72)") (class "Default")
      (node (ref "U6") (pin "72") (pinfunction "72_72") (pintype "bidirectional"))
    )
    (net (code "167") (name "unconnected-(U6-Pad73)") (class "Default")
      (node (ref "U6") (pin "73") (pinfunction "73_73") (pintype "bidirectional"))
    )
    (net (code "168") (name "unconnected-(U6-Pad74)") (class "Default")
      (node (ref "U6") (pin "74") (pinfunction "74_74") (pintype "bidirectional"))
    )
    (net (code "169") (name "unconnected-(U6-Pad75)") (class "Default")
      (node (ref "U6") (pin "75") (pinfunction "75_75") (pintype "bidirectional"))
    )
    (net (code "170") (name "unconnected-(U404-NC-Pad2)") (class "Default")
      (node (ref "U404") (pin "2") (pinfunction "NC_2") (pintype "no_connect"))
    )
    (net (code "171") (name "~{OC}") (class "Default")
      (node (ref "IC401") (pin "10") (pinfunction "~{OVRCUR1}_10") (pintype "input"))
      (node (ref "IC401") (pin "14") (pinfunction "~{OVRCUR2}_14") (pintype "input"))
      (node (ref "IC401") (pin "18") (pinfunction "~{OVRCUR3}_18") (pintype "input"))
      (node (ref "IC401") (pin "22") (pinfunction "~{OVRCUR4}_22") (pintype "input"))
      (node (ref "R402") (pin "2") (pinfunction "2_2") (pintype "passive"))
    )
    (net (code "172") (name "~{PWRON}") (class "Default")
      (node (ref "IC401") (pin "13") (pinfunction "~{PWRON2}_13") (pintype "output"))
      (node (ref "IC401") (pin "17") (pinfunction "~{PWRON3}_17") (pintype "output"))
      (node (ref "IC401") (pin "21") (pinfunction "~{PWRON4}_21") (pintype "output"))
      (node (ref "IC401") (pin "9") (pinfunction "~{PWRON1}_9") (pintype "output"))
    )
  )
)
